# Sheet1.net
KiCad netlist of a schematic drawn in Altium Designer
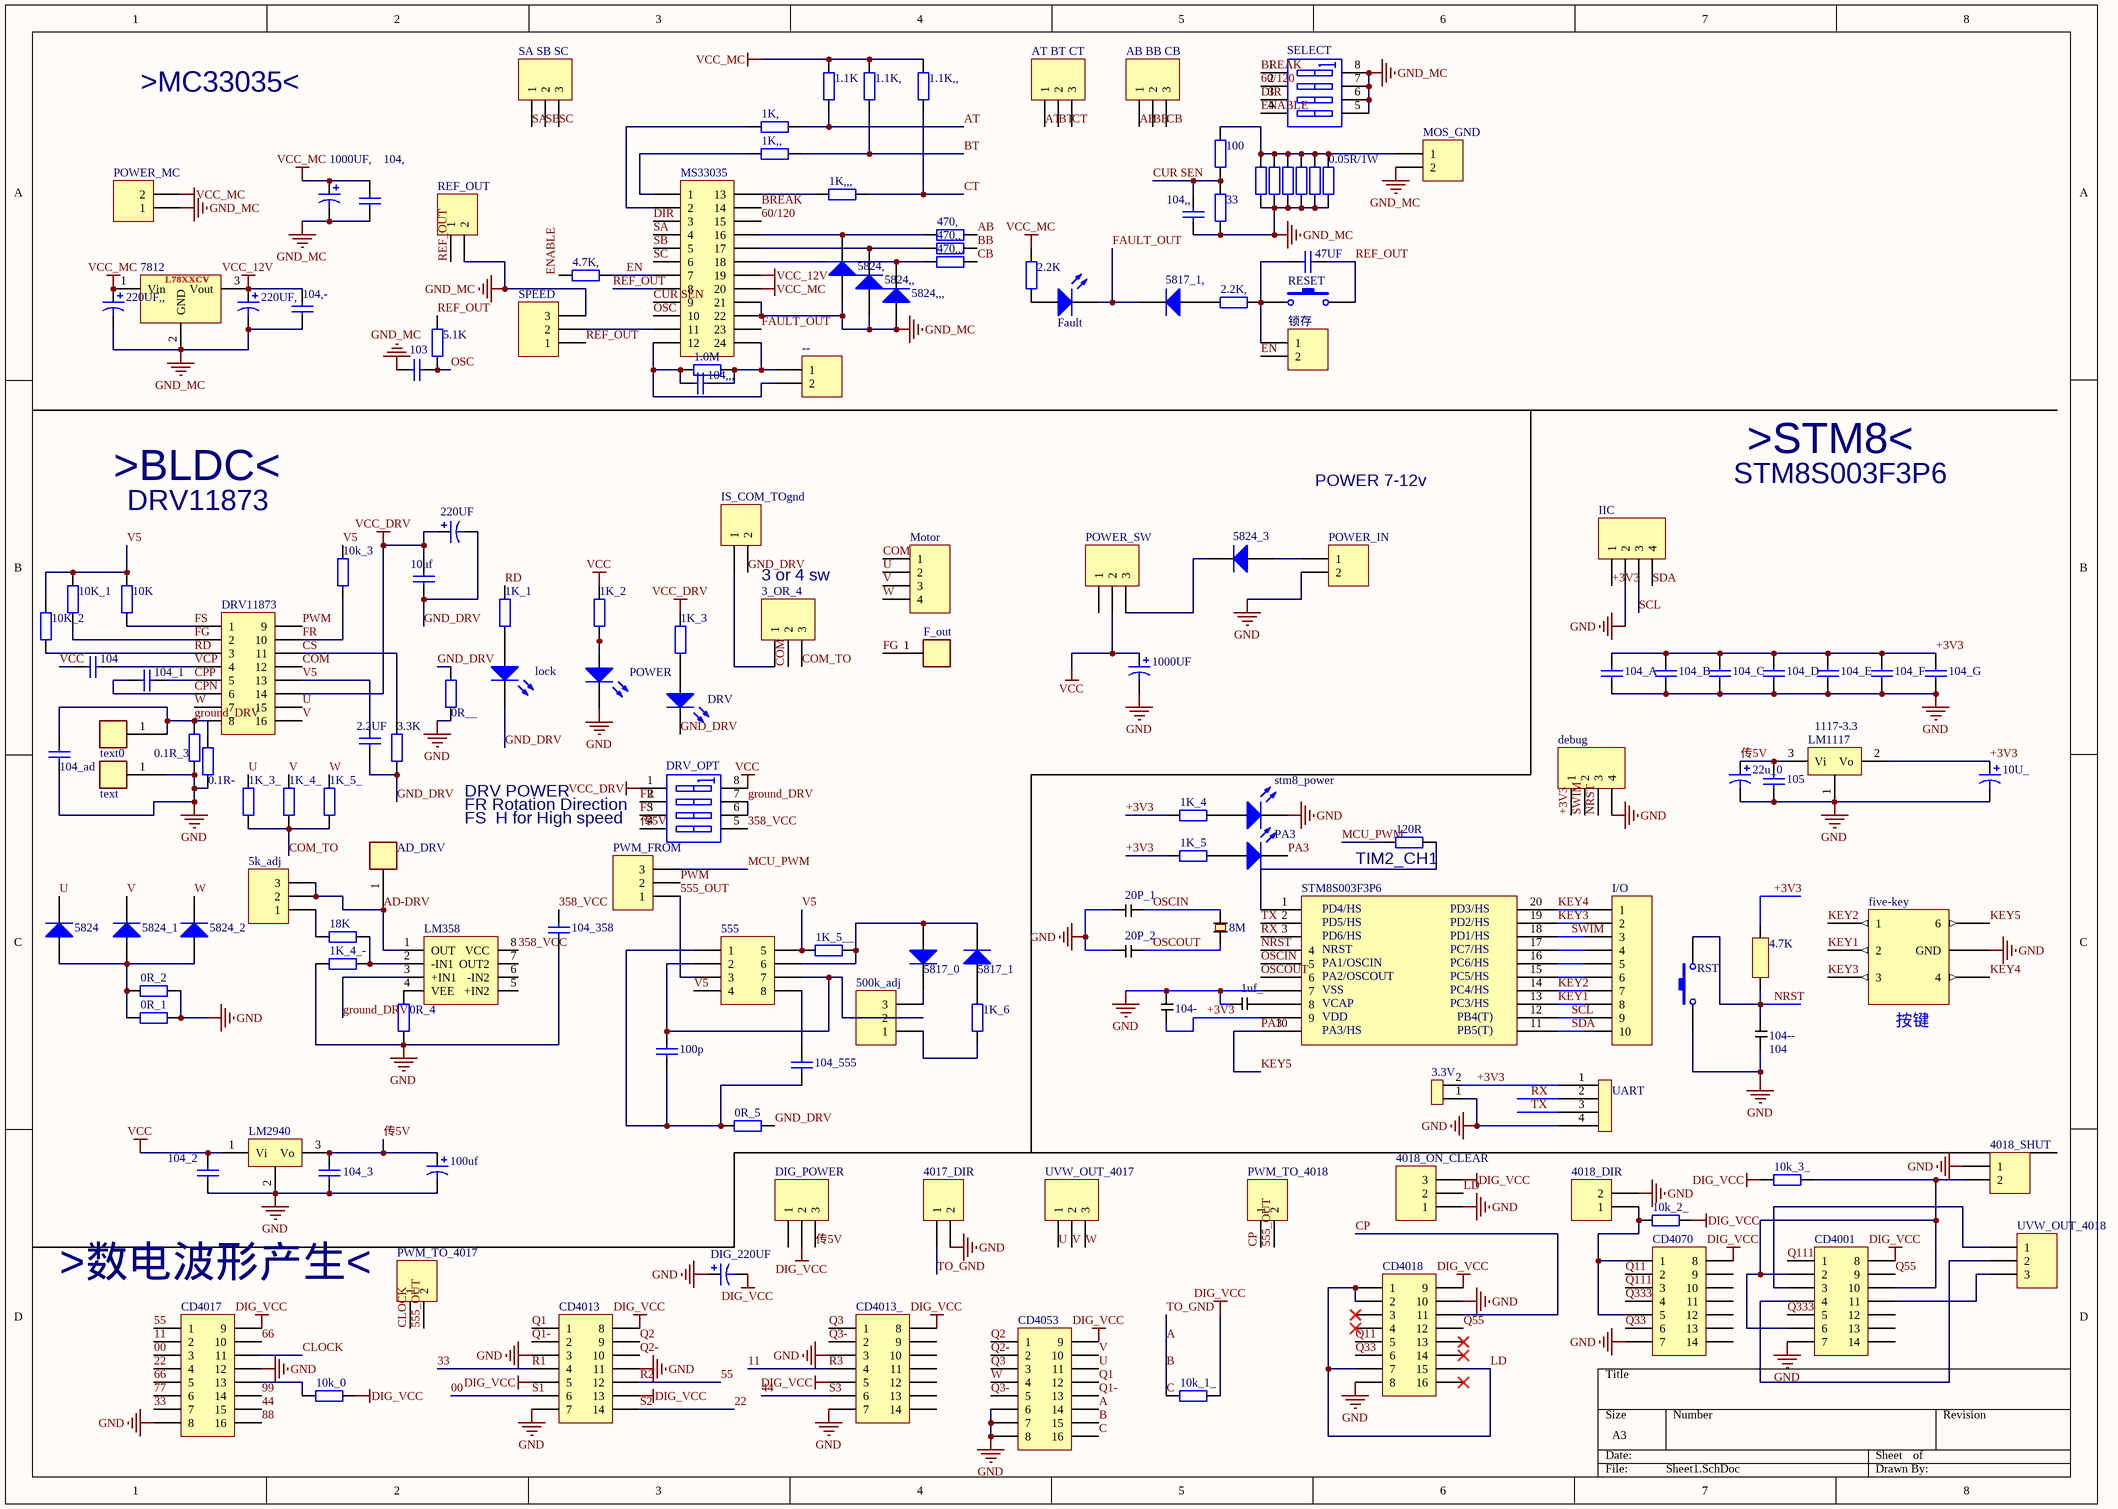
[diagram p0: Sheet1.SchDoc]

(export (version "E")
  (design (tool "Eeschema 10.0.6"))
  (components
    (comp (ref ",,")
      (value "Res2")
      (footprint "RES 0805_1")
      (description "Resistor")
      (fields (field (name "PUBLISHER") "Altium Limited"))
      (libsource (lib "") (part "Res2_3"))
    )
    (comp (ref ",,,")
      (value "Res2")
      (footprint "RES 0805_1")
      (description "Resistor")
      (fields (field (name "PUBLISHER") "Altium Limited"))
      (libsource (lib "") (part "Res2_3"))
    )
    (comp (ref ",,,,")
      (value "Res2")
      (footprint "RES 0805_1")
      (description "Resistor")
      (fields (field (name "PUBLISHER") "Altium Limited"))
      (libsource (lib "") (part "Res2_3"))
    )
    (comp (ref ",,,,,")
      (value "Res2")
      (footprint "RES 0805_1")
      (description "Resistor")
      (fields (field (name "PUBLISHER") "Altium Limited"))
      (libsource (lib "") (part "Res2_3"))
    )
    (comp (ref ",,,,,,")
      (value "Res2")
      (footprint "RES 0805_1")
      (description "Resistor")
      (fields (field (name "PUBLISHER") "Altium Limited"))
      (libsource (lib "") (part "Res2_3"))
    )
    (comp (ref "--")
      (value "Header 2")
      (footprint "HDR1X2")
      (description "Header, 2-Pin")
      (fields (field (name "PUBLISHER") "Altium Limited"))
      (libsource (lib "") (part "Header 2_1"))
    )
    (comp (ref "0.1R-")
      (value "Res2")
      (footprint "RES 0805_1")
      (description "Resistor")
      (fields (field (name "PUBLISHER") "Altium Limited"))
      (libsource (lib "") (part "Res2_1"))
    )
    (comp (ref "0.1R_3")
      (value "Res2")
      (footprint "RES 0805_1")
      (description "Resistor")
      (fields (field (name "PUBLISHER") "Altium Limited"))
      (libsource (lib "") (part "Res2_1"))
    )
    (comp (ref "0.05R/1W")
      (value "Res2")
      (footprint "RES 0805_1")
      (description "Resistor")
      (fields (field (name "PUBLISHER") "Altium Limited"))
      (libsource (lib "") (part "Res2_3"))
    )
    (comp (ref "0R_1")
      (value "Res2")
      (footprint "RES 0805_1")
      (description "Resistor")
      (fields (field (name "PUBLISHER") "Altium Limited"))
      (libsource (lib "") (part "Res2_2"))
    )
    (comp (ref "0R_2")
      (value "Res2")
      (footprint "RES 0805_1")
      (description "Resistor")
      (fields (field (name "PUBLISHER") "Altium Limited"))
      (libsource (lib "") (part "Res2_2"))
    )
    (comp (ref "0R_4")
      (value "Res2")
      (footprint "RES 0805_1")
      (description "Resistor")
      (fields (field (name "PUBLISHER") "Altium Limited"))
      (libsource (lib "") (part "Res2_3"))
    )
    (comp (ref "0R_5")
      (value "Res2")
      (footprint "RES 0805_1")
      (description "Resistor")
      (fields (field (name "PUBLISHER") "Altium Limited"))
      (libsource (lib "Miscellaneous Devices") (part "Res2"))
    )
    (comp (ref "0R__")
      (value "Res2")
      (footprint "RES 0805_1")
      (description "Resistor")
      (fields (field (name "PUBLISHER") "Altium Limited"))
      (libsource (lib "") (part "Res2_1"))
    )
    (comp (ref "1.0M")
      (value "Res2")
      (footprint "RES 0805_1")
      (description "Resistor")
      (fields (field (name "PUBLISHER") "Altium Limited"))
      (libsource (lib "Miscellaneous Devices") (part "Res2"))
    )
    (comp (ref "1.1K")
      (value "Res2")
      (footprint "RES 0805_1")
      (description "Resistor")
      (fields (field (name "PUBLISHER") "Altium Limited"))
      (libsource (lib "") (part "Res2_3"))
    )
    (comp (ref "1.1K,")
      (value "Res2")
      (footprint "RES 0805_1")
      (description "Resistor")
      (fields (field (name "PUBLISHER") "Altium Limited"))
      (libsource (lib "") (part "Res2_3"))
    )
    (comp (ref "1.1K,,")
      (value "Res2")
      (footprint "RES 0805_1")
      (description "Resistor")
      (fields (field (name "PUBLISHER") "Altium Limited"))
      (libsource (lib "") (part "Res2_3"))
    )
    (comp (ref "1K,")
      (value "Res2")
      (footprint "RES 0805_1")
      (description "Resistor")
      (fields (field (name "PUBLISHER") "Altium Limited"))
      (libsource (lib "") (part "Res2_2"))
    )
    (comp (ref "1K,,")
      (value "Res2")
      (footprint "RES 0805_1")
      (description "Resistor")
      (fields (field (name "PUBLISHER") "Altium Limited"))
      (libsource (lib "") (part "Res2_2"))
    )
    (comp (ref "1K,,,")
      (value "Res2")
      (footprint "RES 0805_1")
      (description "Resistor")
      (fields (field (name "PUBLISHER") "Altium Limited"))
      (libsource (lib "") (part "Res2_2"))
    )
    (comp (ref "1K_1")
      (value "Res2")
      (footprint "RES 0805_1")
      (description "Resistor")
      (fields (field (name "PUBLISHER") "Altium Limited"))
      (libsource (lib "") (part "Res2_1"))
    )
    (comp (ref "1K_2")
      (value "Res2")
      (footprint "RES 0805_1")
      (description "Resistor")
      (fields (field (name "PUBLISHER") "Altium Limited"))
      (libsource (lib "") (part "Res2_1"))
    )
    (comp (ref "1K_3")
      (value "Res2")
      (footprint "RES 0805_1")
      (description "Resistor")
      (fields (field (name "PUBLISHER") "Altium Limited"))
      (libsource (lib "") (part "Res2_1"))
    )
    (comp (ref "1K_3_")
      (value "Res2")
      (footprint "RES 0805_1")
      (description "Resistor")
      (fields (field (name "PUBLISHER") "Altium Limited"))
      (libsource (lib "") (part "Res2_1"))
    )
    (comp (ref "1K_4")
      (value "Res2")
      (footprint "RES 0805_1")
      (description "Resistor")
      (fields (field (name "PUBLISHER") "Altium Limited"))
      (libsource (lib "") (part "Res2_2"))
    )
    (comp (ref "1K_4_")
      (value "Res2")
      (footprint "RES 0805_1")
      (description "Resistor")
      (fields (field (name "PUBLISHER") "Altium Limited"))
      (libsource (lib "") (part "Res2_1"))
    )
    (comp (ref "1K_4_-")
      (value "Res2")
      (footprint "RES 0805_1")
      (description "Resistor")
      (fields (field (name "PUBLISHER") "Altium Limited"))
      (libsource (lib "") (part "Res2_2"))
    )
    (comp (ref "1K_5")
      (value "Res2")
      (footprint "RES 0805_1")
      (description "Resistor")
      (fields (field (name "PUBLISHER") "Altium Limited"))
      (libsource (lib "") (part "Res2_2"))
    )
    (comp (ref "1K_5_")
      (value "Res2")
      (footprint "RES 0805_1")
      (description "Resistor")
      (fields (field (name "PUBLISHER") "Altium Limited"))
      (libsource (lib "") (part "Res2_1"))
    )
    (comp (ref "1K_5__")
      (value "Res2")
      (footprint "RES 0805_1")
      (description "Resistor")
      (fields (field (name "PUBLISHER") "Altium Limited"))
      (libsource (lib "") (part "Res2_2"))
    )
    (comp (ref "1K_6")
      (value "Res2")
      (footprint "RES 0805_1")
      (description "Resistor")
      (fields (field (name "PUBLISHER") "Altium Limited"))
      (libsource (lib "") (part "Res2_3"))
    )
    (comp (ref "1uf_") (value "1UF") (footprint "0805") (libsource (lib "My_SCH_lib") (part "CAP 2")))
    (comp (ref "2.2K")
      (value "Res2")
      (footprint "RES 0805_1")
      (description "Resistor")
      (fields (field (name "PUBLISHER") "Altium Limited"))
      (libsource (lib "") (part "Res2_3"))
    )
    (comp (ref "2.2K,")
      (value "Res2")
      (footprint "RES 0805_1")
      (description "Resistor")
      (fields (field (name "PUBLISHER") "Altium Limited"))
      (libsource (lib "Miscellaneous Devices") (part "Res2"))
    )
    (comp (ref "2.2UF")
      (value "Cap")
      (footprint "0805_C")
      (description "Capacitor")
      (fields (field (name "PUBLISHER") "Altium Limited"))
      (libsource (lib "Miscellaneous Devices") (part "Cap"))
    )
    (comp (ref "3.3K")
      (value "Res2")
      (footprint "RES 0805_1")
      (description "Resistor")
      (fields (field (name "PUBLISHER") "Altium Limited"))
      (libsource (lib "") (part "Res2_1"))
    )
    (comp (ref "3.3V") (value "PIN 2") (footprint "HDR1X2") (libsource (lib "My_SCH_lib") (part "PIN 2")))
    (comp (ref "3_OR_4")
      (value "MHDR1X3")
      (footprint "MHDR1X3")
      (description "Header, 3-Pin")
      (fields (field (name "PUBLISHER") "Altium Limited"))
      (libsource (lib "") (part "MHDR1X3_1"))
    )
    (comp (ref "4.7K") (value "4.7K") (footprint "0805-1") (libsource (lib "My_SCH_lib") (part "R")))
    (comp (ref "4.7K,")
      (value "Res2")
      (footprint "RES 0805_1")
      (description "Resistor")
      (fields (field (name "PUBLISHER") "Altium Limited"))
      (libsource (lib "Miscellaneous Devices") (part "Res2"))
    )
    (comp (ref "5.1K")
      (value "Res2")
      (footprint "RES 0805_1")
      (description "Resistor")
      (fields (field (name "PUBLISHER") "Altium Limited"))
      (libsource (lib "") (part "Res2_1"))
    )
    (comp (ref "5k_adj")
      (value "Header 3")
      (footprint "pot（正方形）")
      (description "Header, 3-Pin")
      (fields (field (name "PUBLISHER") "Altium Limited"))
      (libsource (lib "") (part "Header 3_2"))
    )
    (comp (ref "8M") (value "8M") (footprint "XTAL2") (libsource (lib "My_SCH_lib") (part "XTAL")))
    (comp (ref "10K")
      (value "Res2")
      (footprint "RES 0805_1")
      (description "Resistor")
      (fields (field (name "PUBLISHER") "Altium Limited"))
      (libsource (lib "") (part "Res2_1"))
    )
    (comp (ref "10k_0")
      (value "Res2")
      (footprint "RES 0805_1")
      (description "Resistor")
      (fields (field (name "PUBLISHER") "Altium Limited"))
      (libsource (lib "Miscellaneous Devices") (part "Res2"))
    )
    (comp (ref "10K_1")
      (value "Res2")
      (footprint "RES 0805_1")
      (description "Resistor")
      (fields (field (name "PUBLISHER") "Altium Limited"))
      (libsource (lib "") (part "Res2_3"))
    )
    (comp (ref "10k_1_")
      (value "Res2")
      (footprint "RES 0805_1")
      (description "Resistor")
      (fields (field (name "PUBLISHER") "Altium Limited"))
      (libsource (lib "Miscellaneous Devices") (part "Res2"))
    )
    (comp (ref "10K_2")
      (value "Res2")
      (footprint "RES 0805_1")
      (description "Resistor")
      (fields (field (name "PUBLISHER") "Altium Limited"))
      (libsource (lib "") (part "Res2_3"))
    )
    (comp (ref "10k_2_")
      (value "Res2")
      (footprint "RES 0805_1")
      (description "Resistor")
      (fields (field (name "PUBLISHER") "Altium Limited"))
      (libsource (lib "Miscellaneous Devices") (part "Res2"))
    )
    (comp (ref "10k_3")
      (value "Res2")
      (footprint "RES 0805_1")
      (description "Resistor")
      (fields (field (name "PUBLISHER") "Altium Limited"))
      (libsource (lib "") (part "Res2_1"))
    )
    (comp (ref "10k_3_")
      (value "Res2")
      (footprint "RES 0805_1")
      (description "Resistor")
      (fields (field (name "PUBLISHER") "Altium Limited"))
      (libsource (lib "Miscellaneous Devices") (part "Res2"))
    )
    (comp (ref "10uf")
      (value "Cap")
      (footprint "0805_C")
      (description "Capacitor")
      (fields (field (name "PUBLISHER") "Altium Limited"))
      (libsource (lib "Miscellaneous Devices") (part "Cap"))
    )
    (comp (ref "10U_")
      (value "Cap Pol1")
      (footprint "0805-1")
      (description "Polarized Capacitor (Radial)")
      (fields (field (name "PUBLISHER") "Altium Limited"))
      (libsource (lib "Miscellaneous Devices") (part "Cap Pol1"))
    )
    (comp (ref "18K")
      (value "Res2")
      (footprint "RES 0805_1")
      (description "Resistor")
      (fields (field (name "PUBLISHER") "Altium Limited"))
      (libsource (lib "Miscellaneous Devices") (part "Res2"))
    )
    (comp (ref "20P_1") (value "20P") (footprint "0805") (libsource (lib "My_SCH_lib") (part "CAP 2")))
    (comp (ref "20P_2") (value "20P") (footprint "0805") (libsource (lib "My_SCH_lib") (part "CAP 2")))
    (comp (ref "22u_0")
      (value "Cap Pol1")
      (footprint "0805-1")
      (description "Polarized Capacitor (Radial)")
      (fields (field (name "PUBLISHER") "Altium Limited"))
      (libsource (lib "Miscellaneous Devices") (part "Cap Pol1"))
    )
    (comp (ref "33")
      (value "Res2")
      (footprint "RES 0805_1")
      (description "Resistor")
      (fields (field (name "PUBLISHER") "Altium Limited"))
      (libsource (lib "") (part "Res2_1"))
    )
    (comp (ref "47UF")
      (value "Cap")
      (footprint "0805_C")
      (description "Capacitor")
      (fields (field (name "PUBLISHER") "Altium Limited"))
      (libsource (lib "Miscellaneous Devices") (part "Cap"))
    )
    (comp (ref "100")
      (value "Res2")
      (footprint "RES 0805_1")
      (description "Resistor")
      (fields (field (name "PUBLISHER") "Altium Limited"))
      (libsource (lib "") (part "Res2_3"))
    )
    (comp (ref "100p")
      (value "Cap")
      (footprint "0805_C")
      (description "Capacitor")
      (fields (field (name "PUBLISHER") "Altium Limited"))
      (libsource (lib "Miscellaneous Devices") (part "Cap"))
    )
    (comp (ref "100uf")
      (value "Cap Pol1")
      (footprint "capso_8*10")
      (description "Polarized Capacitor (Radial)")
      (fields (field (name "PUBLISHER") "Altium Limited"))
      (libsource (lib "Miscellaneous Devices") (part "Cap Pol1"))
    )
    (comp (ref "103")
      (value "Cap")
      (footprint "0805_C")
      (description "Capacitor")
      (fields (field (name "PUBLISHER") "Altium Limited"))
      (libsource (lib "Miscellaneous Devices") (part "Cap"))
    )
    (comp (ref "104")
      (value "Cap")
      (footprint "0805_C")
      (description "Capacitor")
      (fields (field (name "PUBLISHER") "Altium Limited"))
      (libsource (lib "Miscellaneous Devices") (part "Cap"))
    )
    (comp (ref "104,")
      (value "Cap")
      (footprint "0805_C")
      (description "Capacitor")
      (fields (field (name "PUBLISHER") "Altium Limited"))
      (libsource (lib "Miscellaneous Devices") (part "Cap"))
    )
    (comp (ref "104,,")
      (value "Cap")
      (footprint "0805_C")
      (description "Capacitor")
      (fields (field (name "PUBLISHER") "Altium Limited"))
      (libsource (lib "Miscellaneous Devices") (part "Cap"))
    )
    (comp (ref "104,,,")
      (value "Cap")
      (footprint "0805_C")
      (description "Capacitor")
      (fields (field (name "PUBLISHER") "Altium Limited"))
      (libsource (lib "Miscellaneous Devices") (part "Cap"))
    )
    (comp (ref "104,-")
      (value "Cap")
      (footprint "0805_C")
      (description "Capacitor")
      (fields (field (name "PUBLISHER") "Altium Limited"))
      (libsource (lib "Miscellaneous Devices") (part "Cap"))
    )
    (comp (ref "104-") (value "104") (footprint "0805") (libsource (lib "My_SCH_lib") (part "CAP 2")))
    (comp (ref "104--") (value "104") (footprint "0805") (libsource (lib "My_SCH_lib") (part "CAP 2")))
    (comp (ref "104_1")
      (value "Cap")
      (footprint "0805_C")
      (description "Capacitor")
      (fields (field (name "PUBLISHER") "Altium Limited"))
      (libsource (lib "Miscellaneous Devices") (part "Cap"))
    )
    (comp (ref "104_2")
      (value "Cap")
      (footprint "0805")
      (description "Capacitor")
      (fields (field (name "PUBLISHER") "Altium Limited"))
      (libsource (lib "Miscellaneous Devices") (part "Cap"))
    )
    (comp (ref "104_3")
      (value "Cap")
      (footprint "0805")
      (description "Capacitor")
      (fields (field (name "PUBLISHER") "Altium Limited"))
      (libsource (lib "Miscellaneous Devices") (part "Cap"))
    )
    (comp (ref "104_358")
      (value "Cap")
      (footprint "0805_C")
      (description "Capacitor")
      (fields (field (name "PUBLISHER") "Altium Limited"))
      (libsource (lib "Miscellaneous Devices") (part "Cap"))
    )
    (comp (ref "104_555")
      (value "Cap")
      (footprint "0805_C")
      (description "Capacitor")
      (fields (field (name "PUBLISHER") "Altium Limited"))
      (libsource (lib "Miscellaneous Devices") (part "Cap"))
    )
    (comp (ref "104_A")
      (value "104")
      (footprint "0805")
      (description "Capacitor")
      (fields (field (name "PUBLISHER") "Altium Limited"))
      (libsource (lib "Miscellaneous Devices") (part "Cap"))
    )
    (comp (ref "104_ad")
      (value "Cap")
      (footprint "0805_C")
      (description "Capacitor")
      (fields (field (name "PUBLISHER") "Altium Limited"))
      (libsource (lib "Miscellaneous Devices") (part "Cap"))
    )
    (comp (ref "104_B")
      (value "104")
      (footprint "0805")
      (description "Capacitor")
      (fields (field (name "PUBLISHER") "Altium Limited"))
      (libsource (lib "Miscellaneous Devices") (part "Cap"))
    )
    (comp (ref "104_C")
      (value "104")
      (footprint "0805")
      (description "Capacitor")
      (fields (field (name "PUBLISHER") "Altium Limited"))
      (libsource (lib "Miscellaneous Devices") (part "Cap"))
    )
    (comp (ref "104_D")
      (value "104")
      (footprint "0805")
      (description "Capacitor")
      (fields (field (name "PUBLISHER") "Altium Limited"))
      (libsource (lib "Miscellaneous Devices") (part "Cap"))
    )
    (comp (ref "104_E")
      (value "104")
      (footprint "0805")
      (description "Capacitor")
      (fields (field (name "PUBLISHER") "Altium Limited"))
      (libsource (lib "Miscellaneous Devices") (part "Cap"))
    )
    (comp (ref "104_F")
      (value "104")
      (footprint "0805")
      (description "Capacitor")
      (fields (field (name "PUBLISHER") "Altium Limited"))
      (libsource (lib "Miscellaneous Devices") (part "Cap"))
    )
    (comp (ref "104_G")
      (value "104")
      (footprint "0805")
      (description "Capacitor")
      (fields (field (name "PUBLISHER") "Altium Limited"))
      (libsource (lib "Miscellaneous Devices") (part "Cap"))
    )
    (comp (ref "105")
      (value "105")
      (footprint "0805")
      (description "Capacitor")
      (fields (field (name "PUBLISHER") "Altium Limited"))
      (libsource (lib "Miscellaneous Devices") (part "Cap"))
    )
    (comp (ref "120R")
      (value "Res2")
      (footprint "RES 0805_1")
      (description "Resistor")
      (fields (field (name "PUBLISHER") "Altium Limited"))
      (libsource (lib "") (part "Res2_2"))
    )
    (comp (ref "220UF")
      (value "Cap Pol1")
      (footprint "capso_8*10")
      (description "Polarized Capacitor (Radial)")
      (fields (field (name "PUBLISHER") "Altium Limited"))
      (libsource (lib "Miscellaneous Devices") (part "Cap Pol1"))
    )
    (comp (ref "220UF,")
      (value "Cap Pol1")
      (footprint "capso_8*10")
      (description "Polarized Capacitor (Radial)")
      (fields (field (name "PUBLISHER") "Altium Limited"))
      (libsource (lib "Miscellaneous Devices") (part "Cap Pol1"))
    )
    (comp (ref "220UF,,")
      (value "Cap Pol1")
      (footprint "capso_8*10")
      (description "Polarized Capacitor (Radial)")
      (fields (field (name "PUBLISHER") "Altium Limited"))
      (libsource (lib "Miscellaneous Devices") (part "Cap Pol1"))
    )
    (comp (ref "470,")
      (value "Res2")
      (footprint "RES 0805_1")
      (description "Resistor")
      (fields (field (name "PUBLISHER") "Altium Limited"))
      (libsource (lib "") (part "Res2_2"))
    )
    (comp (ref "470,,")
      (value "Res2")
      (footprint "RES 0805_1")
      (description "Resistor")
      (fields (field (name "PUBLISHER") "Altium Limited"))
      (libsource (lib "") (part "Res2_2"))
    )
    (comp (ref "470,,,")
      (value "Res2")
      (footprint "RES 0805_1")
      (description "Resistor")
      (fields (field (name "PUBLISHER") "Altium Limited"))
      (libsource (lib "") (part "Res2_2"))
    )
    (comp (ref "500k_adj")
      (value "Header 3")
      (footprint "pot（正方形）")
      (description "Header, 3-Pin")
      (fields (field (name "PUBLISHER") "Altium Limited"))
      (libsource (lib "") (part "Header 3_2"))
    )
    (comp (ref "555")
      (value "Header 4X2A")
      (footprint "SOP8")
      (description "Header, 4-Pin, Dual row")
      (fields (field (name "PUBLISHER") "Altium Limited"))
      (libsource (lib "Miscellaneous Connectors") (part "Header 4X2A"))
    )
    (comp (ref "1000UF")
      (value "Cap Pol1")
      (footprint "CAPSO_10*10")
      (description "Polarized Capacitor (Radial)")
      (fields (field (name "PUBLISHER") "Altium Limited"))
      (libsource (lib "Miscellaneous Devices") (part "Cap Pol1"))
    )
    (comp (ref "1000UF,")
      (value "Cap Pol1")
      (footprint "CAPSO_10*10")
      (description "Polarized Capacitor (Radial)")
      (fields (field (name "PUBLISHER") "Altium Limited"))
      (libsource (lib "Miscellaneous Devices") (part "Cap Pol1"))
    )
    (comp (ref "1117-3.3")
      (value "LM1117")
      (footprint "SOT223")
      (libsource (lib "LM1117") (part "Component_1"))
    )
    (comp (ref "4017_DIR")
      (value "Header 2")
      (footprint "HDR1X2")
      (description "Header, 2-Pin")
      (fields (field (name "PUBLISHER") "Altium Limited"))
      (libsource (lib "") (part "Header 2_2"))
    )
    (comp (ref "4018_DIR")
      (value "Header 2")
      (footprint "HDR1X2")
      (description "Header, 2-Pin")
      (fields (field (name "PUBLISHER") "Altium Limited"))
      (libsource (lib "Miscellaneous Connectors") (part "Header 2"))
    )
    (comp (ref "4018_ON_CLEAR")
      (value "MHDR1X3")
      (footprint "MHDR1X3")
      (description "Header, 3-Pin")
      (fields (field (name "PUBLISHER") "Altium Limited"))
      (libsource (lib "Miscellaneous Connectors") (part "MHDR1X3"))
    )
    (comp (ref "4018_SHUT")
      (value "Header 2")
      (footprint "HDR1X2")
      (description "Header, 2-Pin")
      (fields (field (name "PUBLISHER") "Altium Limited"))
      (libsource (lib "") (part "Header 2_1"))
    )
    (comp (ref "5817_0")
      (value "1N5819")
      (footprint "LED_0805")
      (description "1 Amp General Purpose Rectifier")
      (fields (field (name "PUBLISHER") "Altium Limited"))
      (libsource (lib "Miscellaneous Devices") (part "Diode 1N4001"))
    )
    (comp (ref "5817_1")
      (value "1N5819")
      (footprint "LED_0805")
      (description "1 Amp General Purpose Rectifier")
      (fields (field (name "PUBLISHER") "Altium Limited"))
      (libsource (lib "Miscellaneous Devices") (part "Diode 1N4001"))
    )
    (comp (ref "5817_1,")
      (value "1N5819")
      (footprint "LED_0805")
      (description "1 Amp General Purpose Rectifier")
      (fields (field (name "PUBLISHER") "Altium Limited"))
      (libsource (lib "Miscellaneous Devices") (part "Diode 1N4001"))
    )
    (comp (ref "5824")
      (value "1N5819")
      (footprint "DIODE-SMA")
      (description "1 Amp General Purpose Rectifier")
      (fields (field (name "PUBLISHER") "Altium Limited"))
      (libsource (lib "Miscellaneous Devices") (part "Diode 1N4001"))
    )
    (comp (ref "5824,")
      (value "1N5819")
      (footprint "DIODE-SMA")
      (description "1 Amp General Purpose Rectifier")
      (fields (field (name "PUBLISHER") "Altium Limited"))
      (libsource (lib "Miscellaneous Devices") (part "Diode 1N4001"))
    )
    (comp (ref "5824,,")
      (value "1N5819")
      (footprint "DIODE-SMA")
      (description "1 Amp General Purpose Rectifier")
      (fields (field (name "PUBLISHER") "Altium Limited"))
      (libsource (lib "Miscellaneous Devices") (part "Diode 1N4001"))
    )
    (comp (ref "5824,,,")
      (value "1N5819")
      (footprint "DIODE-SMA")
      (description "1 Amp General Purpose Rectifier")
      (fields (field (name "PUBLISHER") "Altium Limited"))
      (libsource (lib "Miscellaneous Devices") (part "Diode 1N4001"))
    )
    (comp (ref "5824_1")
      (value "1N5819")
      (footprint "DIODE-SMA")
      (description "1 Amp General Purpose Rectifier")
      (fields (field (name "PUBLISHER") "Altium Limited"))
      (libsource (lib "Miscellaneous Devices") (part "Diode 1N4001"))
    )
    (comp (ref "5824_2")
      (value "1N5819")
      (footprint "DIODE-SMA")
      (description "1 Amp General Purpose Rectifier")
      (fields (field (name "PUBLISHER") "Altium Limited"))
      (libsource (lib "Miscellaneous Devices") (part "Diode 1N4001"))
    )
    (comp (ref "5824_3")
      (value "1N5819")
      (footprint "DIODE-SMA")
      (description "1 Amp General Purpose Rectifier")
      (fields (field (name "PUBLISHER") "Altium Limited"))
      (libsource (lib "Miscellaneous Devices") (part "Diode 1N4001"))
    )
    (comp (ref "7812")
      (value "L78XXCV")
      (footprint "TO-220B")
      (description "ST POSITIVE VOLTAGE REGULATORS")
      (libsource (lib "电源管理") (part "L78XXCV"))
    )
    (comp (ref "AB BB CB")
      (value "Header 3")
      (footprint "HDR1X3")
      (description "Header, 3-Pin")
      (fields (field (name "PUBLISHER") "Altium Limited"))
      (libsource (lib "Miscellaneous Connectors") (part "Header 3"))
    )
    (comp (ref "AD_DRV") (value "1PIN") (footprint "P") (libsource (lib "") (part "1PIN_2")))
    (comp (ref "AT BT CT")
      (value "Header 3")
      (footprint "HDR1X3")
      (description "Header, 3-Pin")
      (fields (field (name "PUBLISHER") "Altium Limited"))
      (libsource (lib "Miscellaneous Connectors") (part "Header 3"))
    )
    (comp (ref "CD4001")
      (value "Header 7X2A")
      (footprint "DIP14")
      (description "Header, 7-Pin, Dual row")
      (fields (field (name "PUBLISHER") "Altium Limited"))
      (libsource (lib "Miscellaneous Connectors") (part "Header 7X2A"))
    )
    (comp (ref "CD4013")
      (value "Header 7X2A")
      (footprint "SOP-14P")
      (description "Header, 7-Pin, Dual row")
      (fields (field (name "PUBLISHER") "Altium Limited"))
      (libsource (lib "Miscellaneous Connectors") (part "Header 7X2A"))
    )
    (comp (ref "CD4013_")
      (value "Header 7X2A")
      (footprint "SOP-14P")
      (description "Header, 7-Pin, Dual row")
      (fields (field (name "PUBLISHER") "Altium Limited"))
      (libsource (lib "Miscellaneous Connectors") (part "Header 7X2A"))
    )
    (comp (ref "CD4017")
      (value "Header 8X2A")
      (footprint "sop16(2003)")
      (description "Header, 8-Pin, Dual row")
      (fields (field (name "PUBLISHER") "Altium Limited"))
      (libsource (lib "Miscellaneous Connectors") (part "Header 8X2A"))
    )
    (comp (ref "CD4018")
      (value "Header 8X2A")
      (footprint "DIP16")
      (description "Header, 8-Pin, Dual row")
      (fields (field (name "PUBLISHER") "Altium Limited"))
      (libsource (lib "Miscellaneous Connectors") (part "Header 8X2A"))
    )
    (comp (ref "CD4053")
      (value "Header 8X2A")
      (footprint "sop16(2003)")
      (description "Header, 8-Pin, Dual row")
      (fields (field (name "PUBLISHER") "Altium Limited"))
      (libsource (lib "Miscellaneous Connectors") (part "Header 8X2A"))
    )
    (comp (ref "CD4070")
      (value "Header 7X2A")
      (footprint "DIP14")
      (description "Header, 7-Pin, Dual row")
      (fields (field (name "PUBLISHER") "Altium Limited"))
      (libsource (lib "Miscellaneous Connectors") (part "Header 7X2A"))
    )
    (comp (ref "debug")
      (value "Header 4")
      (footprint "HDR1X4")
      (description "Header, 4-Pin")
      (fields (field (name "PUBLISHER") "Altium Limited"))
      (libsource (lib "") (part "Header 4_1"))
    )
    (comp (ref "DIG_220UF")
      (value "Cap Pol1")
      (footprint "capso_8*10")
      (description "Polarized Capacitor (Radial)")
      (fields (field (name "PUBLISHER") "Altium Limited"))
      (libsource (lib "Miscellaneous Devices") (part "Cap Pol1"))
    )
    (comp (ref "DIG_POWER")
      (value "MHDR1X3")
      (footprint "MHDR1X3")
      (description "Header, 3-Pin")
      (fields (field (name "PUBLISHER") "Altium Limited"))
      (libsource (lib "") (part "MHDR1X3_1"))
    )
    (comp (ref "DRV") (value "LED") (footprint "LED_0805") (libsource (lib "主板库") (part "LED")))
    (comp (ref "DRV11873")
      (value "Header 8X2A")
      (footprint "TSSOP16")
      (description "Header, 8-Pin, Dual row")
      (fields (field (name "PUBLISHER") "Altium Limited"))
      (libsource (lib "Miscellaneous Connectors") (part "Header 8X2A"))
    )
    (comp (ref "DRV_OPT")
      (value "SW DIP-4")
      (footprint "SW8_4BIT")
      (description "编码开关")
      (fields (field (name "PUBLISHER") "Altium Limited"))
      (libsource (lib "Fszhang") (part "SW DIP-4"))
    )
    (comp (ref "Fault") (value "LED") (footprint "LED_0805") (libsource (lib "主板库") (part "LED")))
    (comp (ref "five-key") (value "five_key") (footprint "五向按键") (libsource (lib "VET6") (part "five_key")))
    (comp (ref "F_out") (value "1PIN") (footprint "P") (libsource (lib "") (part "1PIN_1")))
    (comp (ref "I/O")
      (value "Header 10")
      (footprint "HDR1X10")
      (description "Header, 10-Pin")
      (fields (field (name "PUBLISHER") "Altium Limited"))
      (libsource (lib "Miscellaneous Connectors") (part "Header 10"))
    )
    (comp (ref "IIC")
      (value "Header 4")
      (footprint "HDR1X4")
      (description "Header, 4-Pin")
      (fields (field (name "PUBLISHER") "Altium Limited"))
      (libsource (lib "") (part "Header 4_1"))
    )
    (comp (ref "IS_COM_TOgnd")
      (value "Header 2")
      (footprint "HDR1X2")
      (description "Header, 2-Pin")
      (fields (field (name "PUBLISHER") "Altium Limited"))
      (libsource (lib "") (part "Header 2_2"))
    )
    (comp (ref "LM358") (value "10358") (footprint "SOP8") (libsource (lib "集成块") (part "10358")))
    (comp (ref "LM2940") (value "LM2940_2") (footprint "SOT223") (libsource (lib "主板库") (part "LM2940")))
    (comp (ref "lock") (value "LED") (footprint "LED_0805") (libsource (lib "主板库") (part "LED")))
    (comp (ref "MOS_GND")
      (value "Header 2")
      (footprint "ED120/2DS_1")
      (description "Header, 2-Pin")
      (fields (field (name "PUBLISHER") "Altium Limited"))
      (libsource (lib "") (part "Header 2_1"))
    )
    (comp (ref "Motor")
      (value "Header 4")
      (footprint "ED120/4DS_1")
      (description "Header, 4-Pin")
      (fields (field (name "PUBLISHER") "Altium Limited"))
      (libsource (lib "Miscellaneous Connectors") (part "Header 4"))
    )
    (comp (ref "MS33035")
      (value "Header 12X2A")
      (footprint "SO-24W")
      (description "Header, 12-Pin, Dual row")
      (fields (field (name "PUBLISHER") "Altium Limited"))
      (libsource (lib "Miscellaneous Connectors") (part "Header 12X2A"))
    )
    (comp (ref "PA3") (value "LED") (footprint "LED_0805") (libsource (lib "主板库") (part "LED")))
    (comp (ref "POWER") (value "LED") (footprint "LED_0805") (libsource (lib "主板库") (part "LED")))
    (comp (ref "POWER_IN")
      (value "Header 2")
      (footprint "ED120/2DS_1")
      (description "Header, 2-Pin")
      (fields (field (name "PUBLISHER") "Altium Limited"))
      (libsource (lib "") (part "Header 2_1"))
    )
    (comp (ref "POWER_MC")
      (value "Header 2")
      (footprint "ED120/2DS_1")
      (description "Header, 2-Pin")
      (fields (field (name "PUBLISHER") "Altium Limited"))
      (libsource (lib "Miscellaneous Connectors") (part "Header 2"))
    )
    (comp (ref "POWER_SW")
      (value "MHDR1X3")
      (footprint "MHDR1X3")
      (description "Header, 3-Pin")
      (fields (field (name "PUBLISHER") "Altium Limited"))
      (libsource (lib "") (part "MHDR1X3_1"))
    )
    (comp (ref "PWM_FROM")
      (value "MHDR1X3")
      (footprint "MHDR1X3")
      (description "Header, 3-Pin")
      (fields (field (name "PUBLISHER") "Altium Limited"))
      (libsource (lib "Miscellaneous Connectors") (part "MHDR1X3"))
    )
    (comp (ref "PWM_TO_4017")
      (value "Header 2")
      (footprint "HDR1X2")
      (description "Header, 2-Pin")
      (fields (field (name "PUBLISHER") "Altium Limited"))
      (libsource (lib "") (part "Header 2_2"))
    )
    (comp (ref "PWM_TO_4018")
      (value "Header 2")
      (footprint "HDR1X2")
      (description "Header, 2-Pin")
      (fields (field (name "PUBLISHER") "Altium Limited"))
      (libsource (lib "") (part "Header 2_2"))
    )
    (comp (ref "REF_OUT")
      (value "Header 2")
      (footprint "HDR1X2")
      (description "Header, 2-Pin")
      (fields (field (name "PUBLISHER") "Altium Limited"))
      (libsource (lib "") (part "Header 2_2"))
    )
    (comp (ref "RESET")
      (value "SW-PB")
      (footprint "SW_PB2_A1")
      (description "微动开关")
      (fields (field (name "PUBLISHER") "Altium Limited"))
      (libsource (lib "Fszhang") (part "SW-PB"))
    )
    (comp (ref "RST")
      (value "SW-PB")
      (footprint "SW_PB2_A1")
      (description "微动开关")
      (fields (field (name "PUBLISHER") "Altium Limited"))
      (libsource (lib "Fszhang") (part "SW-PB"))
    )
    (comp (ref "SA SB SC")
      (value "Header 3")
      (footprint "HDR1X3")
      (description "Header, 3-Pin")
      (fields (field (name "PUBLISHER") "Altium Limited"))
      (libsource (lib "Miscellaneous Connectors") (part "Header 3"))
    )
    (comp (ref "SELECT")
      (value "SW DIP-4")
      (footprint "SW8_4BIT")
      (description "编码开关")
      (fields (field (name "PUBLISHER") "Altium Limited"))
      (libsource (lib "Fszhang") (part "SW DIP-4"))
    )
    (comp (ref "SPEED")
      (value "MHDR1X3")
      (footprint "pot（正方形）")
      (description "Header, 3-Pin")
      (fields (field (name "PUBLISHER") "Altium Limited"))
      (libsource (lib "Miscellaneous Connectors") (part "MHDR1X3"))
    )
    (comp (ref "STM8S003F3P6")
      (value "STM8S003F3P6")
      (footprint "TSSOP20")
      (libsource (lib "My_SCH_lib") (part "STM8S003F3P6"))
    )
    (comp (ref "stm8_power") (value "LED") (footprint "LED_0805") (libsource (lib "主板库") (part "LED")))
    (comp (ref "text") (value "1PIN") (footprint "P") (libsource (lib "常用器件库_SCH") (part "1PIN")))
    (comp (ref "text0") (value "1PIN") (footprint "P") (libsource (lib "常用器件库_SCH") (part "1PIN")))
    (comp (ref "UART") (value "PIN 4") (footprint "HDR1X4") (libsource (lib "My_SCH_lib") (part "PIN 4")))
    (comp (ref "UVW_OUT_4017")
      (value "Header 3")
      (footprint "HDR1X3")
      (description "Header, 3-Pin")
      (fields (field (name "PUBLISHER") "Altium Limited"))
      (libsource (lib "Miscellaneous Connectors") (part "Header 3"))
    )
    (comp (ref "UVW_OUT_4018")
      (value "Header 3")
      (footprint "HDR1X3")
      (description "Header, 3-Pin")
      (fields (field (name "PUBLISHER") "Altium Limited"))
      (libsource (lib "") (part "Header 3_1"))
    )
    (comp (ref "锁存")
      (value "Header 2")
      (footprint "HDR1X2")
      (description "Header, 2-Pin")
      (fields (field (name "PUBLISHER") "Altium Limited"))
      (libsource (lib "") (part "Header 2_1"))
    )
  )
  (nets
    (net (code "1") (name "/+3V3") (class "Default")
      (node (ref "104-") (pin "1") (pinfunction "1_1") (pintype "passive"))
      (node (ref "104_A") (pin "1") (pinfunction "1_1") (pintype "passive"))
      (node (ref "104_B") (pin "1") (pinfunction "1_1") (pintype "passive"))
      (node (ref "104_C") (pin "1") (pinfunction "1_1") (pintype "passive"))
      (node (ref "104_D") (pin "1") (pinfunction "1_1") (pintype "passive"))
      (node (ref "104_E") (pin "1") (pinfunction "1_1") (pintype "passive"))
      (node (ref "104_F") (pin "1") (pinfunction "1_1") (pintype "passive"))
      (node (ref "104_G") (pin "1") (pinfunction "1_1") (pintype "passive"))
      (node (ref "10U_") (pin "1") (pinfunction "1_1") (pintype "passive"))
      (node (ref "1117-3.3") (pin "2") (pinfunction "Vo_2") (pintype "passive"))
      (node (ref "1K_4") (pin "2") (pinfunction "2_2") (pintype "passive"))
      (node (ref "1K_5") (pin "2") (pinfunction "2_2") (pintype "passive"))
      (node (ref "3.3V") (pin "2") (pinfunction "2_2") (pintype "passive"))
      (node (ref "4.7K") (pin "2") (pintype "passive"))
      (node (ref "IIC") (pin "1") (pinfunction "1_1") (pintype "passive"))
      (node (ref "STM8S003F3P6") (pin "9") (pinfunction "9_9") (pintype "passive"))
      (node (ref "UART") (pin "1") (pinfunction "1_1") (pintype "passive"))
      (node (ref "debug") (pin "1") (pinfunction "1_1") (pintype "passive"))
    )
    (net (code "2") (name "/00") (class "Default")
      (node (ref "CD4013") (pin "6") (pinfunction "6_6") (pintype "passive"))
      (node (ref "CD4017") (pin "3") (pinfunction "3_3") (pintype "passive"))
    )
    (net (code "3") (name "/11") (class "Default")
      (node (ref "CD4013_") (pin "4") (pinfunction "4_4") (pintype "passive"))
      (node (ref "CD4017") (pin "2") (pinfunction "2_2") (pintype "passive"))
    )
    (net (code "4") (name "/22") (class "Default")
      (node (ref "CD4013") (pin "14") (pinfunction "14_14") (pintype "passive"))
      (node (ref "CD4017") (pin "4") (pinfunction "4_4") (pintype "passive"))
    )
    (net (code "5") (name "/33") (class "Default")
      (node (ref "CD4013") (pin "4") (pinfunction "4_4") (pintype "passive"))
      (node (ref "CD4017") (pin "7") (pinfunction "7_7") (pintype "passive"))
    )
    (net (code "6") (name "/44") (class "Default")
      (node (ref "CD4013_") (pin "6") (pinfunction "6_6") (pintype "passive"))
      (node (ref "CD4017") (pin "15") (pinfunction "15_15") (pintype "passive"))
    )
    (net (code "7") (name "/55") (class "Default")
      (node (ref "CD4013") (pin "12") (pinfunction "12_12") (pintype "passive"))
      (node (ref "CD4017") (pin "1") (pinfunction "1_1") (pintype "passive"))
    )
    (net (code "8") (name "/60{slash}120") (class "Default")
      (node (ref "MS33035") (pin "15") (pinfunction "15_15") (pintype "passive"))
      (node (ref "SELECT") (pin "2") (pinfunction "A2_2") (pintype "passive"))
    )
    (net (code "9") (name "/66") (class "Default")
      (node (ref "CD4017") (pin "10") (pinfunction "10_10") (pintype "passive"))
      (node (ref "CD4017") (pin "5") (pinfunction "5_5") (pintype "passive"))
    )
    (net (code "10") (name "/77") (class "Default")
      (node (ref "CD4017") (pin "6") (pinfunction "6_6") (pintype "passive"))
    )
    (net (code "11") (name "/88") (class "Default")
      (node (ref "CD4017") (pin "16") (pinfunction "16_16") (pintype "passive"))
    )
    (net (code "12") (name "/99") (class "Default")
      (node (ref "CD4017") (pin "14") (pinfunction "14_14") (pintype "passive"))
    )
    (net (code "13") (name "/358_VCC") (class "Default")
      (node (ref "104_358") (pin "2") (pinfunction "2_2") (pintype "passive"))
      (node (ref "DRV_OPT") (pin "5") (pinfunction "B4_5") (pintype "passive"))
      (node (ref "LM358") (pin "8") (pinfunction "VCC_8") (pintype "passive"))
    )
    (net (code "14") (name "/555_OUT") (class "Default")
      (node (ref "555") (pin "3") (pinfunction "3_3") (pintype "passive"))
      (node (ref "PWM_FROM") (pin "1") (pinfunction "1_1") (pintype "passive"))
      (node (ref "PWM_TO_4017") (pin "2") (pinfunction "2_2") (pintype "passive"))
      (node (ref "PWM_TO_4018") (pin "2") (pinfunction "2_2") (pintype "passive"))
    )
    (net (code "15") (name "/A") (class "Default")
      (node (ref "10k_1_") (pin "1") (pinfunction "1_1") (pintype "passive"))
      (node (ref "4017_DIR") (pin "1") (pinfunction "1_1") (pintype "passive"))
      (node (ref "CD4053") (pin "14") (pinfunction "14_14") (pintype "passive"))
      (node (ref "CD4053") (pin "15") (pinfunction "15_15") (pintype "passive"))
      (node (ref "CD4053") (pin "16") (pinfunction "16_16") (pintype "passive"))
    )
    (net (code "16") (name "/AB") (class "Default")
      (node (ref "470,") (pin "1") (pinfunction "1_1") (pintype "passive"))
      (node (ref "AB BB CB") (pin "1") (pinfunction "1_1") (pintype "passive"))
    )
    (net (code "17") (name "/AD-DRV") (class "Default")
      (node (ref "5k_adj") (pin "2") (pinfunction "2_2") (pintype "passive"))
      (node (ref "5k_adj") (pin "3") (pinfunction "3_3") (pintype "passive"))
      (node (ref "AD_DRV") (pin "1") (pintype "passive"))
      (node (ref "LM358") (pin "1") (pinfunction "OUT_1") (pintype "passive"))
    )
    (net (code "18") (name "/AT") (class "Default")
      (node (ref "1.1K") (pin "2") (pinfunction "2_2") (pintype "passive"))
      (node (ref "1K,") (pin "1") (pinfunction "1_1") (pintype "passive"))
      (node (ref "AT BT CT") (pin "1") (pinfunction "1_1") (pintype "passive"))
    )
    (net (code "19") (name "/BB") (class "Default")
      (node (ref "470,,") (pin "1") (pinfunction "1_1") (pintype "passive"))
      (node (ref "AB BB CB") (pin "2") (pinfunction "2_2") (pintype "passive"))
    )
    (net (code "20") (name "/BREAK") (class "Default")
      (node (ref "MS33035") (pin "14") (pinfunction "14_14") (pintype "passive"))
      (node (ref "SELECT") (pin "1") (pinfunction "A1_1") (pintype "passive"))
    )
    (net (code "21") (name "/BT") (class "Default")
      (node (ref "1.1K,") (pin "2") (pinfunction "2_2") (pintype "passive"))
      (node (ref "1K,,") (pin "1") (pinfunction "1_1") (pintype "passive"))
      (node (ref "AT BT CT") (pin "2") (pinfunction "2_2") (pintype "passive"))
    )
    (net (code "22") (name "/CB") (class "Default")
      (node (ref "470,,,") (pin "1") (pinfunction "1_1") (pintype "passive"))
      (node (ref "AB BB CB") (pin "3") (pinfunction "3_3") (pintype "passive"))
    )
    (net (code "23") (name "/CLOCK") (class "Default")
      (node (ref "CD4017") (pin "11") (pinfunction "11_11") (pintype "passive"))
      (node (ref "PWM_TO_4017") (pin "1") (pinfunction "1_1") (pintype "passive"))
    )
    (net (code "24") (name "/COM") (class "Default")
      (node (ref "3_OR_4") (pin "2") (pinfunction "2_2") (pintype "passive"))
      (node (ref "DRV11873") (pin "12") (pinfunction "12_12") (pintype "passive"))
      (node (ref "Motor") (pin "1") (pinfunction "1_1") (pintype "passive"))
    )
    (net (code "25") (name "/COM_TO") (class "Default")
      (node (ref "1K_3_") (pin "1") (pinfunction "1_1") (pintype "passive"))
      (node (ref "1K_4_") (pin "1") (pinfunction "1_1") (pintype "passive"))
      (node (ref "1K_5_") (pin "1") (pinfunction "1_1") (pintype "passive"))
      (node (ref "3_OR_4") (pin "3") (pinfunction "3_3") (pintype "passive"))
    )
    (net (code "26") (name "/CP") (class "Default")
      (node (ref "CD4018") (pin "11") (pinfunction "11_11") (pintype "passive"))
      (node (ref "PWM_TO_4018") (pin "1") (pinfunction "1_1") (pintype "passive"))
    )
    (net (code "27") (name "/CPN") (class "Default")
      (node (ref "104_1") (pin "1") (pinfunction "1_1") (pintype "passive"))
      (node (ref "DRV11873") (pin "6") (pinfunction "6_6") (pintype "passive"))
    )
    (net (code "28") (name "/CPP") (class "Default")
      (node (ref "104_1") (pin "2") (pinfunction "2_2") (pintype "passive"))
      (node (ref "DRV11873") (pin "5") (pinfunction "5_5") (pintype "passive"))
    )
    (net (code "29") (name "/CS") (class "Default")
      (node (ref "3.3K") (pin "2") (pinfunction "2_2") (pintype "passive"))
      (node (ref "DRV11873") (pin "11") (pinfunction "11_11") (pintype "passive"))
    )
    (net (code "30") (name "/CT") (class "Default")
      (node (ref "1.1K,,") (pin "2") (pinfunction "2_2") (pintype "passive"))
      (node (ref "1K,,,") (pin "1") (pinfunction "1_1") (pintype "passive"))
      (node (ref "AT BT CT") (pin "3") (pinfunction "3_3") (pintype "passive"))
    )
    (net (code "31") (name "/CUR SEN") (class "Default")
      (node (ref "100") (pin "2") (pinfunction "2_2") (pintype "passive"))
      (node (ref "104,,") (pin "1") (pinfunction "1_1") (pintype "passive"))
      (node (ref "33") (pin "2") (pinfunction "2_2") (pintype "passive"))
      (node (ref "MS33035") (pin "9") (pinfunction "9_9") (pintype "passive"))
    )
    (net (code "32") (name "/DIR") (class "Default")
      (node (ref "MS33035") (pin "3") (pinfunction "3_3") (pintype "passive"))
      (node (ref "SELECT") (pin "3") (pinfunction "A3_3") (pintype "passive"))
    )
    (net (code "33") (name "/EN") (class "Default")
      (node (ref "4.7K,") (pin "2") (pinfunction "2_2") (pintype "passive"))
      (node (ref "MS33035") (pin "7") (pinfunction "7_7") (pintype "passive"))
      (node (ref "锁存") (pin "2") (pinfunction "2_2") (pintype "passive"))
    )
    (net (code "34") (name "/ENABLE") (class "Default")
      (node (ref "4.7K,") (pin "1") (pinfunction "1_1") (pintype "passive"))
      (node (ref "SELECT") (pin "4") (pinfunction "A4_4") (pintype "passive"))
    )
    (net (code "35") (name "/FAULT_OUT") (class "Default")
      (node (ref "5817_1,") (pin "2") (pinfunction "K_2") (pintype "passive"))
      (node (ref "Fault") (pin "2") (pinfunction "K_2") (pintype "passive"))
      (node (ref "MS33035") (pin "23") (pinfunction "23_23") (pintype "passive"))
    )
    (net (code "36") (name "/FG") (class "Default")
      (node (ref "10K_1") (pin "2") (pinfunction "2_2") (pintype "passive"))
      (node (ref "DRV11873") (pin "2") (pinfunction "2_2") (pintype "passive"))
      (node (ref "F_out") (pin "1") (pintype "passive"))
    )
    (net (code "37") (name "/FR") (class "Default")
      (node (ref "10k_3") (pin "1") (pinfunction "1_1") (pintype "passive"))
      (node (ref "DRV11873") (pin "10") (pinfunction "10_10") (pintype "passive"))
      (node (ref "DRV_OPT") (pin "2") (pinfunction "A2_2") (pintype "passive"))
    )
    (net (code "38") (name "/FS") (class "Default")
      (node (ref "10K") (pin "1") (pinfunction "1_1") (pintype "passive"))
      (node (ref "DRV11873") (pin "1") (pinfunction "1_1") (pintype "passive"))
      (node (ref "DRV_OPT") (pin "3") (pinfunction "A3_3") (pintype "passive"))
    )
    (net (code "39") (name "/GND_DRV") (class "Default")
      (node (ref "0R_5") (pin "2") (pinfunction "2_2") (pintype "passive"))
      (node (ref "0R__") (pin "2") (pinfunction "2_2") (pintype "passive"))
      (node (ref "10uf") (pin "1") (pinfunction "1_1") (pintype "passive"))
      (node (ref "2.2UF") (pin "1") (pinfunction "1_1") (pintype "passive"))
      (node (ref "220UF") (pin "2") (pinfunction "2_2") (pintype "passive"))
      (node (ref "3.3K") (pin "1") (pinfunction "1_1") (pintype "passive"))
      (node (ref "DRV") (pin "2") (pinfunction "K_2") (pintype "passive"))
      (node (ref "IS_COM_TOgnd") (pin "2") (pinfunction "2_2") (pintype "passive"))
      (node (ref "lock") (pin "2") (pinfunction "K_2") (pintype "passive"))
    )
    (net (code "40") (name "/KEY1") (class "Default")
      (node (ref "I/O") (pin "8") (pinfunction "8_8") (pintype "passive"))
      (node (ref "STM8S003F3P6") (pin "13") (pinfunction "TIM1_CH3[TLI][TIM1_CH1N]_13") (pintype "passive"))
      (node (ref "five-key") (pin "2") (pinfunction "2_2") (pintype "output"))
    )
    (net (code "41") (name "/KEY2") (class "Default")
      (node (ref "I/O") (pin "7") (pinfunction "7_7") (pintype "passive"))
      (node (ref "STM8S003F3P6") (pin "14") (pinfunction "TIM1_CH4/CLK_CCO/AIN2[TIM1_CH2N]_14") (pintype "passive"))
      (node (ref "five-key") (pin "1") (pinfunction "1_1") (pintype "output"))
    )
    (net (code "42") (name "/KEY3") (class "Default")
      (node (ref "I/O") (pin "2") (pinfunction "2_2") (pintype "passive"))
      (node (ref "STM8S003F3P6") (pin "19") (pinfunction "AIN3[TIM2_CH3]_19") (pintype "passive"))
      (node (ref "five-key") (pin "3") (pinfunction "3_3") (pintype "output"))
    )
    (net (code "43") (name "/KEY4") (class "Default")
      (node (ref "I/O") (pin "1") (pinfunction "1_1") (pintype "passive"))
      (node (ref "STM8S003F3P6") (pin "20") (pinfunction "AIN4/TIM2_CH2/ADC_ETR_20") (pintype "passive"))
      (node (ref "five-key") (pin "4") (pinfunction "4_4") (pintype "output"))
    )
    (net (code "44") (name "/KEY5") (class "Default")
      (node (ref "PA3") (pin "2") (pinfunction "K_2") (pintype "passive"))
      (node (ref "STM8S003F3P6") (pin "10") (pinfunction "[SPI_NSS]TIM2_CH3/HS_10") (pintype "passive"))
      (node (ref "five-key") (pin "6") (pinfunction "6_6") (pintype "output"))
    )
    (net (code "45") (name "/LD") (class "Default")
      (node (ref "4018_ON_CLEAR") (pin "2") (pinfunction "2_2") (pintype "passive"))
      (node (ref "CD4018") (pin "1") (pinfunction "1_1") (pintype "passive"))
      (node (ref "CD4018") (pin "15") (pinfunction "15_15") (pintype "passive"))
      (node (ref "CD4018") (pin "2") (pinfunction "2_2") (pintype "passive"))
      (node (ref "CD4018") (pin "7") (pinfunction "7_7") (pintype "passive"))
    )
    (net (code "46") (name "/MCU_PWM") (class "Default")
      (node (ref "120R") (pin "2") (pinfunction "2_2") (pintype "passive"))
      (node (ref "PWM_FROM") (pin "3") (pinfunction "3_3") (pintype "passive"))
    )
    (net (code "47") (name "/NRST") (class "Default")
      (node (ref "104--") (pin "2") (pinfunction "2_2") (pintype "passive"))
      (node (ref "4.7K") (pin "1") (pintype "passive"))
      (node (ref "RST") (pin "2") (pinfunction "2_2") (pintype "passive"))
      (node (ref "STM8S003F3P6") (pin "4") (pinfunction "4_4") (pintype "passive"))
      (node (ref "debug") (pin "3") (pinfunction "3_3") (pintype "passive"))
    )
    (net (code "48") (name "/OSC") (class "Default")
      (node (ref "103") (pin "1") (pinfunction "1_1") (pintype "passive"))
      (node (ref "5.1K") (pin "1") (pinfunction "1_1") (pintype "passive"))
      (node (ref "MS33035") (pin "10") (pinfunction "10_10") (pintype "passive"))
    )
    (net (code "49") (name "/OSCIN") (class "Default")
      (node (ref "20P_1") (pin "2") (pinfunction "2_2") (pintype "passive"))
      (node (ref "8M") (pin "2") (pinfunction "2_2") (pintype "passive"))
      (node (ref "STM8S003F3P6") (pin "5") (pinfunction "5_5") (pintype "passive"))
    )
    (net (code "50") (name "/OSCOUT") (class "Default")
      (node (ref "20P_2") (pin "2") (pinfunction "2_2") (pintype "passive"))
      (node (ref "8M") (pin "1") (pinfunction "1_1") (pintype "passive"))
      (node (ref "STM8S003F3P6") (pin "6") (pinfunction "6_6") (pintype "passive"))
    )
    (net (code "51") (name "/PWM") (class "Default")
      (node (ref "DRV11873") (pin "9") (pinfunction "9_9") (pintype "passive"))
      (node (ref "PWM_FROM") (pin "2") (pinfunction "2_2") (pintype "passive"))
    )
    (net (code "52") (name "/Q1") (class "Default")
      (node (ref "CD4013") (pin "1") (pinfunction "1_1") (pintype "passive"))
      (node (ref "CD4053") (pin "12") (pinfunction "12_12") (pintype "passive"))
    )
    (net (code "53") (name "/Q1-") (class "Default")
      (node (ref "CD4013") (pin "2") (pinfunction "2_2") (pintype "passive"))
      (node (ref "CD4053") (pin "13") (pinfunction "13_13") (pintype "passive"))
    )
    (net (code "54") (name "/Q2") (class "Default")
      (node (ref "CD4013") (pin "9") (pinfunction "9_9") (pintype "passive"))
      (node (ref "CD4053") (pin "1") (pinfunction "1_1") (pintype "passive"))
    )
    (net (code "55") (name "/Q2-") (class "Default")
      (node (ref "CD4013") (pin "10") (pinfunction "10_10") (pintype "passive"))
      (node (ref "CD4053") (pin "2") (pinfunction "2_2") (pintype "passive"))
    )
    (net (code "56") (name "/Q3") (class "Default")
      (node (ref "CD4013_") (pin "1") (pinfunction "1_1") (pintype "passive"))
      (node (ref "CD4053") (pin "3") (pinfunction "3_3") (pintype "passive"))
    )
    (net (code "57") (name "/Q3-") (class "Default")
      (node (ref "CD4013_") (pin "2") (pinfunction "2_2") (pintype "passive"))
      (node (ref "CD4053") (pin "5") (pinfunction "5_5") (pintype "passive"))
    )
    (net (code "58") (name "/Q11") (class "Default")
      (node (ref "CD4018") (pin "5") (pinfunction "5_5") (pintype "passive"))
      (node (ref "CD4070") (pin "2") (pinfunction "2_2") (pintype "passive"))
    )
    (net (code "59") (name "/Q33") (class "Default")
      (node (ref "CD4018") (pin "6") (pinfunction "6_6") (pintype "passive"))
      (node (ref "CD4070") (pin "6") (pinfunction "6_6") (pintype "passive"))
    )
    (net (code "60") (name "/Q55") (class "Default")
      (node (ref "CD4001") (pin "9") (pinfunction "9_9") (pintype "passive"))
      (node (ref "CD4018") (pin "12") (pinfunction "12_12") (pintype "passive"))
    )
    (net (code "61") (name "/Q111") (class "Default")
      (node (ref "CD4001") (pin "1") (pinfunction "1_1") (pintype "passive"))
      (node (ref "CD4070") (pin "3") (pinfunction "3_3") (pintype "passive"))
    )
    (net (code "62") (name "/Q333") (class "Default")
      (node (ref "CD4001") (pin "5") (pinfunction "5_5") (pintype "passive"))
      (node (ref "CD4070") (pin "4") (pinfunction "4_4") (pintype "passive"))
    )
    (net (code "63") (name "/RD") (class "Default")
      (node (ref "10K_2") (pin "2") (pinfunction "2_2") (pintype "passive"))
      (node (ref "1K_1") (pin "2") (pinfunction "2_2") (pintype "passive"))
      (node (ref "DRV11873") (pin "3") (pinfunction "3_3") (pintype "passive"))
    )
    (net (code "64") (name "/REF_OUT") (class "Default")
      (node (ref "47UF") (pin "1") (pinfunction "1_1") (pintype "passive"))
      (node (ref "5.1K") (pin "2") (pinfunction "2_2") (pintype "passive"))
      (node (ref "MS33035") (pin "8") (pinfunction "8_8") (pintype "passive"))
      (node (ref "REF_OUT") (pin "1") (pinfunction "1_1") (pintype "passive"))
      (node (ref "RESET") (pin "2") (pinfunction "2_2") (pintype "passive"))
      (node (ref "SPEED") (pin "1") (pinfunction "1_1") (pintype "passive"))
    )
    (net (code "65") (name "/RX") (class "Default")
      (node (ref "STM8S003F3P6") (pin "3") (pinfunction "UART1_RX/AIN6/HS_3") (pintype "passive"))
      (node (ref "UART") (pin "2") (pinfunction "2_2") (pintype "passive"))
    )
    (net (code "66") (name "/SA") (class "Default")
      (node (ref "MS33035") (pin "4") (pinfunction "4_4") (pintype "passive"))
      (node (ref "SA SB SC") (pin "1") (pinfunction "1_1") (pintype "passive"))
    )
    (net (code "67") (name "/SB") (class "Default")
      (node (ref "MS33035") (pin "5") (pinfunction "5_5") (pintype "passive"))
      (node (ref "SA SB SC") (pin "2") (pinfunction "2_2") (pintype "passive"))
    )
    (net (code "68") (name "/SC") (class "Default")
      (node (ref "MS33035") (pin "6") (pinfunction "6_6") (pintype "passive"))
      (node (ref "SA SB SC") (pin "3") (pinfunction "3_3") (pintype "passive"))
    )
    (net (code "69") (name "/SCL") (class "Default")
      (node (ref "I/O") (pin "9") (pinfunction "9_9") (pintype "passive"))
      (node (ref "IIC") (pin "3") (pinfunction "3_3") (pintype "passive"))
      (node (ref "STM8S003F3P6") (pin "12") (pinfunction "I2C_SCL[ADC_ETR]_12") (pintype "passive"))
    )
    (net (code "70") (name "/SDA") (class "Default")
      (node (ref "I/O") (pin "10") (pinfunction "10_10") (pintype "passive"))
      (node (ref "IIC") (pin "4") (pinfunction "4_4") (pintype "passive"))
      (node (ref "STM8S003F3P6") (pin "11") (pinfunction "I2C_SDA[TIM1_BKIN]_11") (pintype "passive"))
    )
    (net (code "71") (name "/SWIM") (class "Default")
      (node (ref "I/O") (pin "3") (pinfunction "3_3") (pintype "passive"))
      (node (ref "STM8S003F3P6") (pin "18") (pinfunction "SWIM_18") (pintype "passive"))
      (node (ref "debug") (pin "2") (pinfunction "2_2") (pintype "passive"))
    )
    (net (code "72") (name "/TX") (class "Default")
      (node (ref "STM8S003F3P6") (pin "2") (pinfunction "UART1_TX/AIN5/HS_2") (pintype "passive"))
      (node (ref "UART") (pin "3") (pinfunction "3_3") (pintype "passive"))
    )
    (net (code "73") (name "/U") (class "Default")
      (node (ref "1K_3_") (pin "2") (pinfunction "2_2") (pintype "passive"))
      (node (ref "5824") (pin "2") (pinfunction "K_2") (pintype "passive"))
      (node (ref "CD4053") (pin "11") (pinfunction "11_11") (pintype "passive"))
      (node (ref "DRV11873") (pin "15") (pinfunction "15_15") (pintype "passive"))
      (node (ref "Motor") (pin "2") (pinfunction "2_2") (pintype "passive"))
      (node (ref "UVW_OUT_4017") (pin "1") (pinfunction "1_1") (pintype "passive"))
    )
    (net (code "74") (name "/V") (class "Default")
      (node (ref "1K_4_") (pin "2") (pinfunction "2_2") (pintype "passive"))
      (node (ref "5824_1") (pin "2") (pinfunction "K_2") (pintype "passive"))
      (node (ref "CD4053") (pin "10") (pinfunction "10_10") (pintype "passive"))
      (node (ref "DRV11873") (pin "16") (pinfunction "16_16") (pintype "passive"))
      (node (ref "Motor") (pin "3") (pinfunction "3_3") (pintype "passive"))
      (node (ref "UVW_OUT_4017") (pin "2") (pinfunction "2_2") (pintype "passive"))
    )
    (net (code "75") (name "/V5") (class "Default")
      (node (ref "10K") (pin "2") (pinfunction "2_2") (pintype "passive"))
      (node (ref "10K_1") (pin "1") (pinfunction "1_1") (pintype "passive"))
      (node (ref "10K_2") (pin "1") (pinfunction "1_1") (pintype "passive"))
      (node (ref "10k_3") (pin "2") (pinfunction "2_2") (pintype "passive"))
      (node (ref "1K_5__") (pin "2") (pinfunction "2_2") (pintype "passive"))
      (node (ref "2.2UF") (pin "2") (pinfunction "2_2") (pintype "passive"))
      (node (ref "555") (pin "4") (pinfunction "4_4") (pintype "passive"))
      (node (ref "555") (pin "5") (pinfunction "5_5") (pintype "passive"))
      (node (ref "DRV11873") (pin "13") (pinfunction "13_13") (pintype "passive"))
    )
    (net (code "76") (name "/VCP") (class "Default")
      (node (ref "104") (pin "2") (pinfunction "2_2") (pintype "passive"))
      (node (ref "DRV11873") (pin "4") (pinfunction "4_4") (pintype "passive"))
    )
    (net (code "77") (name "/W") (class "Default")
      (node (ref "1K_5_") (pin "2") (pinfunction "2_2") (pintype "passive"))
      (node (ref "5824_2") (pin "2") (pinfunction "K_2") (pintype "passive"))
      (node (ref "CD4053") (pin "4") (pinfunction "4_4") (pintype "passive"))
      (node (ref "DRV11873") (pin "7") (pinfunction "7_7") (pintype "passive"))
      (node (ref "Motor") (pin "4") (pinfunction "4_4") (pintype "passive"))
      (node (ref "UVW_OUT_4017") (pin "3") (pinfunction "3_3") (pintype "passive"))
    )
    (net (code "78") (name "/ground_DRV") (class "Default")
      (node (ref "0.1R-") (pin "2") (pinfunction "2_2") (pintype "passive"))
      (node (ref "0.1R_3") (pin "2") (pinfunction "2_2") (pintype "passive"))
      (node (ref "104_ad") (pin "2") (pinfunction "2_2") (pintype "passive"))
      (node (ref "DRV11873") (pin "8") (pinfunction "8_8") (pintype "passive"))
      (node (ref "DRV_OPT") (pin "6") (pinfunction "B3_6") (pintype "passive"))
      (node (ref "DRV_OPT") (pin "7") (pinfunction "B2_7") (pintype "passive"))
      (node (ref "LM358") (pin "3") (pinfunction "+IN1_3") (pintype "passive"))
      (node (ref "text0") (pin "1") (pintype "passive"))
    )
    (net (code "79") (name "/传5V") (class "Default")
      (node (ref "100uf") (pin "1") (pinfunction "1_1") (pintype "passive"))
      (node (ref "104_3") (pin "2") (pinfunction "2_2") (pintype "passive"))
      (node (ref "105") (pin "1") (pinfunction "1_1") (pintype "passive"))
      (node (ref "1117-3.3") (pin "3") (pinfunction "Vi_3") (pintype "passive"))
      (node (ref "22u_0") (pin "1") (pinfunction "1_1") (pintype "passive"))
      (node (ref "DIG_POWER") (pin "3") (pinfunction "3_3") (pintype "passive"))
      (node (ref "DRV_OPT") (pin "4") (pinfunction "A4_4") (pintype "passive"))
      (node (ref "LM2940") (pin "3") (pinfunction "Vo_3") (pintype "passive"))
    )
    (net (code "80") (name "DIG_VCC") (class "Default")
      (node (ref "10k_0") (pin "2") (pinfunction "2_2") (pintype "passive"))
      (node (ref "10k_1_") (pin "2") (pinfunction "2_2") (pintype "passive"))
      (node (ref "10k_2_") (pin "2") (pinfunction "2_2") (pintype "passive"))
      (node (ref "10k_3_") (pin "1") (pinfunction "1_1") (pintype "passive"))
      (node (ref "4018_ON_CLEAR") (pin "3") (pinfunction "3_3") (pintype "passive"))
      (node (ref "CD4001") (pin "8") (pinfunction "8_8") (pintype "passive"))
      (node (ref "CD4013") (pin "13") (pinfunction "13_13") (pintype "passive"))
      (node (ref "CD4013") (pin "5") (pinfunction "5_5") (pintype "passive"))
      (node (ref "CD4013") (pin "8") (pinfunction "8_8") (pintype "passive"))
      (node (ref "CD4013_") (pin "5") (pinfunction "5_5") (pintype "passive"))
      (node (ref "CD4013_") (pin "8") (pinfunction "8_8") (pintype "passive"))
      (node (ref "CD4017") (pin "9") (pinfunction "9_9") (pintype "passive"))
      (node (ref "CD4018") (pin "9") (pinfunction "9_9") (pintype "passive"))
      (node (ref "CD4053") (pin "9") (pinfunction "9_9") (pintype "passive"))
      (node (ref "CD4070") (pin "8") (pinfunction "8_8") (pintype "passive"))
      (node (ref "DIG_220UF") (pin "2") (pinfunction "2_2") (pintype "passive"))
      (node (ref "DIG_POWER") (pin "2") (pinfunction "2_2") (pintype "passive"))
    )
    (net (code "81") (name "GND") (class "Default")
      (node (ref "0.1R-") (pin "1") (pinfunction "1_1") (pintype "passive"))
      (node (ref "0.1R_3") (pin "1") (pinfunction "1_1") (pintype "passive"))
      (node (ref "0R_1") (pin "1") (pinfunction "1_1") (pintype "passive"))
      (node (ref "0R_2") (pin "1") (pinfunction "1_1") (pintype "passive"))
      (node (ref "0R_4") (pin "2") (pinfunction "2_2") (pintype "passive"))
      (node (ref "0R__") (pin "1") (pinfunction "1_1") (pintype "passive"))
      (node (ref "1000UF") (pin "2") (pinfunction "2_2") (pintype "passive"))
      (node (ref "100uf") (pin "2") (pinfunction "2_2") (pintype "passive"))
      (node (ref "104-") (pin "2") (pinfunction "2_2") (pintype "passive"))
      (node (ref "104--") (pin "1") (pinfunction "1_1") (pintype "passive"))
      (node (ref "104_2") (pin "1") (pinfunction "1_1") (pintype "passive"))
      (node (ref "104_3") (pin "1") (pinfunction "1_1") (pintype "passive"))
      (node (ref "104_358") (pin "1") (pinfunction "1_1") (pintype "passive"))
      (node (ref "104_A") (pin "2") (pinfunction "2_2") (pintype "passive"))
      (node (ref "104_B") (pin "2") (pinfunction "2_2") (pintype "passive"))
      (node (ref "104_C") (pin "2") (pinfunction "2_2") (pintype "passive"))
      (node (ref "104_D") (pin "2") (pinfunction "2_2") (pintype "passive"))
      (node (ref "104_E") (pin "2") (pinfunction "2_2") (pintype "passive"))
      (node (ref "104_F") (pin "2") (pinfunction "2_2") (pintype "passive"))
      (node (ref "104_G") (pin "2") (pinfunction "2_2") (pintype "passive"))
      (node (ref "104_ad") (pin "1") (pinfunction "1_1") (pintype "passive"))
      (node (ref "105") (pin "2") (pinfunction "2_2") (pintype "passive"))
      (node (ref "10U_") (pin "2") (pinfunction "2_2") (pintype "passive"))
      (node (ref "1117-3.3") (pin "1") (pinfunction "COM_1") (pintype "passive"))
      (node (ref "1K_4_-") (pin "2") (pinfunction "2_2") (pintype "passive"))
      (node (ref "1uf_") (pin "2") (pinfunction "2_2") (pintype "passive"))
      (node (ref "20P_1") (pin "1") (pinfunction "1_1") (pintype "passive"))
      (node (ref "20P_2") (pin "1") (pinfunction "1_1") (pintype "passive"))
      (node (ref "22u_0") (pin "2") (pinfunction "2_2") (pintype "passive"))
      (node (ref "3.3V") (pin "1") (pinfunction "1_1") (pintype "passive"))
      (node (ref "4017_DIR") (pin "2") (pinfunction "2_2") (pintype "passive"))
      (node (ref "4018_DIR") (pin "2") (pinfunction "2_2") (pintype "passive"))
      (node (ref "4018_ON_CLEAR") (pin "1") (pinfunction "1_1") (pintype "passive"))
      (node (ref "4018_SHUT") (pin "1") (pinfunction "1_1") (pintype "passive"))
      (node (ref "CD4001") (pin "7") (pinfunction "7_7") (pintype "passive"))
      (node (ref "CD4013") (pin "11") (pinfunction "11_11") (pintype "passive"))
      (node (ref "CD4013") (pin "3") (pinfunction "3_3") (pintype "passive"))
      (node (ref "CD4013") (pin "7") (pinfunction "7_7") (pintype "passive"))
      (node (ref "CD4013_") (pin "3") (pinfunction "3_3") (pintype "passive"))
      (node (ref "CD4013_") (pin "7") (pinfunction "7_7") (pintype "passive"))
      (node (ref "CD4017") (pin "12") (pinfunction "12_12") (pintype "passive"))
      (node (ref "CD4017") (pin "8") (pinfunction "8_8") (pintype "passive"))
      (node (ref "CD4018") (pin "10") (pinfunction "10_10") (pintype "passive"))
      (node (ref "CD4018") (pin "8") (pinfunction "8_8") (pintype "passive"))
      (node (ref "CD4053") (pin "6") (pinfunction "6_6") (pintype "passive"))
      (node (ref "CD4053") (pin "7") (pinfunction "7_7") (pintype "passive"))
      (node (ref "CD4053") (pin "8") (pinfunction "8_8") (pintype "passive"))
      (node (ref "CD4070") (pin "7") (pinfunction "7_7") (pintype "passive"))
      (node (ref "DIG_220UF") (pin "1") (pinfunction "1_1") (pintype "passive"))
      (node (ref "IIC") (pin "2") (pinfunction "2_2") (pintype "passive"))
      (node (ref "LM2940") (pin "2") (pinfunction "2_2") (pintype "passive"))
      (node (ref "POWER") (pin "2") (pinfunction "K_2") (pintype "passive"))
      (node (ref "POWER_IN") (pin "2") (pinfunction "2_2") (pintype "passive"))
      (node (ref "RST") (pin "1") (pinfunction "1_1") (pintype "passive"))
      (node (ref "STM8S003F3P6") (pin "7") (pinfunction "7_7") (pintype "passive"))
      (node (ref "UART") (pin "4") (pinfunction "4_4") (pintype "passive"))
      (node (ref "debug") (pin "4") (pinfunction "4_4") (pintype "passive"))
      (node (ref "five-key") (pin "5") (pinfunction "GND_5") (pintype "power_in"))
      (node (ref "stm8_power") (pin "2") (pinfunction "K_2") (pintype "passive"))
      (node (ref "text") (pin "1") (pintype "passive"))
    )
    (net (code "82") (name "GND_MC") (class "Default")
      (node (ref ",,") (pin "2") (pinfunction "2_2") (pintype "passive"))
      (node (ref ",,,") (pin "2") (pinfunction "2_2") (pintype "passive"))
      (node (ref ",,,,") (pin "2") (pinfunction "2_2") (pintype "passive"))
      (node (ref ",,,,,") (pin "2") (pinfunction "2_2") (pintype "passive"))
      (node (ref ",,,,,,") (pin "2") (pinfunction "2_2") (pintype "passive"))
      (node (ref "0.05R/1W") (pin "2") (pinfunction "2_2") (pintype "passive"))
      (node (ref "1000UF,") (pin "2") (pinfunction "2_2") (pintype "passive"))
      (node (ref "103") (pin "2") (pinfunction "2_2") (pintype "passive"))
      (node (ref "104,") (pin "1") (pinfunction "1_1") (pintype "passive"))
      (node (ref "104,,") (pin "2") (pinfunction "2_2") (pintype "passive"))
      (node (ref "104,-") (pin "1") (pinfunction "1_1") (pintype "passive"))
      (node (ref "220UF,") (pin "2") (pinfunction "2_2") (pintype "passive"))
      (node (ref "220UF,,") (pin "2") (pinfunction "2_2") (pintype "passive"))
      (node (ref "33") (pin "1") (pinfunction "1_1") (pintype "passive"))
      (node (ref "5824,") (pin "1") (pinfunction "A_1") (pintype "passive"))
      (node (ref "5824,,") (pin "1") (pinfunction "A_1") (pintype "passive"))
      (node (ref "5824,,,") (pin "1") (pinfunction "A_1") (pintype "passive"))
      (node (ref "7812") (pin "2") (pinfunction "GND_2") (pintype "passive"))
      (node (ref "MOS_GND") (pin "2") (pinfunction "2_2") (pintype "passive"))
      (node (ref "MS33035") (pin "21") (pinfunction "21_21") (pintype "passive"))
      (node (ref "MS33035") (pin "22") (pinfunction "22_22") (pintype "passive"))
      (node (ref "POWER_MC") (pin "1") (pinfunction "1_1") (pintype "passive"))
      (node (ref "REF_OUT") (pin "2") (pinfunction "2_2") (pintype "passive"))
      (node (ref "SELECT") (pin "5") (pinfunction "B4_5") (pintype "passive"))
      (node (ref "SELECT") (pin "6") (pinfunction "B3_6") (pintype "passive"))
      (node (ref "SELECT") (pin "7") (pinfunction "B2_7") (pintype "passive"))
      (node (ref "SELECT") (pin "8") (pinfunction "B1_8") (pintype "passive"))
      (node (ref "SPEED") (pin "3") (pinfunction "3_3") (pintype "passive"))
    )
    (net (code "83") (name "Net-(,,,,,,-Pad1)") (class "Default")
      (node (ref ",,") (pin "1") (pinfunction "1_1") (pintype "passive"))
      (node (ref ",,,") (pin "1") (pinfunction "1_1") (pintype "passive"))
      (node (ref ",,,,") (pin "1") (pinfunction "1_1") (pintype "passive"))
      (node (ref ",,,,,") (pin "1") (pinfunction "1_1") (pintype "passive"))
      (node (ref ",,,,,,") (pin "1") (pinfunction "1_1") (pintype "passive"))
      (node (ref "0.05R/1W") (pin "1") (pinfunction "1_1") (pintype "passive"))
      (node (ref "100") (pin "1") (pinfunction "1_1") (pintype "passive"))
      (node (ref "MOS_GND") (pin "1") (pinfunction "1_1") (pintype "passive"))
    )
    (net (code "84") (name "Net-(---Pad1)") (class "Default")
      (node (ref "--") (pin "1") (pinfunction "1_1") (pintype "passive"))
      (node (ref "1.0M") (pin "2") (pinfunction "2_2") (pintype "passive"))
      (node (ref "104,,,") (pin "1") (pinfunction "1_1") (pintype "passive"))
      (node (ref "MS33035") (pin "24") (pinfunction "24_24") (pintype "passive"))
    )
    (net (code "85") (name "Net-(---Pad2)") (class "Default")
      (node (ref "--") (pin "2") (pinfunction "2_2") (pintype "passive"))
      (node (ref "1.0M") (pin "1") (pinfunction "1_1") (pintype "passive"))
      (node (ref "104,,,") (pin "2") (pinfunction "2_2") (pintype "passive"))
      (node (ref "MS33035") (pin "12") (pinfunction "12_12") (pintype "passive"))
    )
    (net (code "86") (name "Net-(0R_5-Pad1)") (class "Default")
      (node (ref "0R_5") (pin "1") (pinfunction "1_1") (pintype "passive"))
      (node (ref "100p") (pin "1") (pinfunction "1_1") (pintype "passive"))
      (node (ref "104_555") (pin "1") (pinfunction "1_1") (pintype "passive"))
      (node (ref "555") (pin "1") (pinfunction "1_1") (pintype "passive"))
    )
    (net (code "87") (name "Net-(1K,,,-Pad2)") (class "Default")
      (node (ref "1K,,,") (pin "2") (pinfunction "2_2") (pintype "passive"))
      (node (ref "MS33035") (pin "13") (pinfunction "13_13") (pintype "passive"))
    )
    (net (code "88") (name "Net-(1K,,-Pad2)") (class "Default")
      (node (ref "1K,,") (pin "2") (pinfunction "2_2") (pintype "passive"))
      (node (ref "MS33035") (pin "1") (pinfunction "1_1") (pintype "passive"))
    )
    (net (code "89") (name "Net-(1K,-Pad2)") (class "Default")
      (node (ref "1K,") (pin "2") (pinfunction "2_2") (pintype "passive"))
      (node (ref "MS33035") (pin "2") (pinfunction "2_2") (pintype "passive"))
    )
    (net (code "90") (name "Net-(1K_6-Pad2)") (class "Default")
      (node (ref "1K_6") (pin "2") (pinfunction "2_2") (pintype "passive"))
      (node (ref "500k_adj") (pin "1") (pinfunction "1_1") (pintype "passive"))
    )
    (net (code "91") (name "Net-(1uf_-Pad1)") (class "Default")
      (node (ref "1uf_") (pin "1") (pinfunction "1_1") (pintype "passive"))
      (node (ref "STM8S003F3P6") (pin "8") (pinfunction "8_8") (pintype "passive"))
    )
    (net (code "92") (name "Net-(2.2K,-Pad2)") (class "Default")
      (node (ref "2.2K,") (pin "2") (pinfunction "2_2") (pintype "passive"))
      (node (ref "47UF") (pin "2") (pinfunction "2_2") (pintype "passive"))
      (node (ref "RESET") (pin "1") (pinfunction "1_1") (pintype "passive"))
      (node (ref "锁存") (pin "1") (pinfunction "1_1") (pintype "passive"))
    )
    (net (code "93") (name "Net-(3_OR_4-Pad1)") (class "Default")
      (node (ref "3_OR_4") (pin "1") (pinfunction "1_1") (pintype "passive"))
      (node (ref "IS_COM_TOgnd") (pin "1") (pinfunction "1_1") (pintype "passive"))
    )
    (net (code "94") (name "Net-(10k_0-Pad1)") (class "Default")
      (node (ref "10k_0") (pin "1") (pinfunction "1_1") (pintype "passive"))
      (node (ref "CD4017") (pin "13") (pinfunction "13_13") (pintype "passive"))
    )
    (net (code "95") (name "Net-(10k_2_-Pad1)") (class "Default")
      (node (ref "10k_2_") (pin "1") (pinfunction "1_1") (pintype "passive"))
      (node (ref "4018_DIR") (pin "1") (pinfunction "1_1") (pintype "passive"))
      (node (ref "CD4070") (pin "1") (pinfunction "1_1") (pintype "passive"))
      (node (ref "CD4070") (pin "5") (pinfunction "5_5") (pintype "passive"))
    )
    (net (code "96") (name "Net-(10k_3_-Pad2)") (class "Default")
      (node (ref "10k_3_") (pin "2") (pinfunction "2_2") (pintype "passive"))
      (node (ref "4018_SHUT") (pin "2") (pinfunction "2_2") (pintype "passive"))
      (node (ref "CD4001") (pin "10") (pinfunction "10_10") (pintype "passive"))
      (node (ref "CD4001") (pin "2") (pinfunction "2_2") (pintype "passive"))
      (node (ref "CD4001") (pin "6") (pinfunction "6_6") (pintype "passive"))
    )
    (net (code "97") (name "Net-(18K-Pad1)") (class "Default")
      (node (ref "18K") (pin "1") (pinfunction "1_1") (pintype "passive"))
      (node (ref "5k_adj") (pin "1") (pinfunction "1_1") (pintype "passive"))
    )
    (net (code "98") (name "Net-(100p-Pad2)") (class "Default")
      (node (ref "100p") (pin "2") (pinfunction "2_2") (pintype "passive"))
      (node (ref "500k_adj") (pin "2") (pinfunction "2_2") (pintype "passive"))
      (node (ref "555") (pin "2") (pinfunction "2_2") (pintype "passive"))
      (node (ref "555") (pin "7") (pinfunction "7_7") (pintype "passive"))
    )
    (net (code "99") (name "Net-(104_555-Pad2)") (class "Default")
      (node (ref "104_555") (pin "2") (pinfunction "2_2") (pintype "passive"))
      (node (ref "555") (pin "8") (pinfunction "8_8") (pintype "passive"))
    )
    (net (code "100") (name "Net-(5817_0-A)") (class "Default")
      (node (ref "1K_5__") (pin "1") (pinfunction "1_1") (pintype "passive"))
      (node (ref "555") (pin "6") (pinfunction "6_6") (pintype "passive"))
      (node (ref "5817_0") (pin "1") (pinfunction "A_1") (pintype "passive"))
      (node (ref "5817_1") (pin "2") (pinfunction "K_2") (pintype "passive"))
    )
    (net (code "101") (name "Net-(5817_0-K)") (class "Default")
      (node (ref "500k_adj") (pin "3") (pinfunction "3_3") (pintype "passive"))
      (node (ref "5817_0") (pin "2") (pinfunction "K_2") (pintype "passive"))
    )
    (net (code "102") (name "Net-(5817_1,-A)") (class "Default")
      (node (ref "2.2K,") (pin "1") (pinfunction "1_1") (pintype "passive"))
      (node (ref "5817_1,") (pin "1") (pinfunction "A_1") (pintype "passive"))
    )
    (net (code "103") (name "Net-(5817_1-A)") (class "Default")
      (node (ref "1K_6") (pin "1") (pinfunction "1_1") (pintype "passive"))
      (node (ref "5817_1") (pin "1") (pinfunction "A_1") (pintype "passive"))
    )
    (net (code "104") (name "Net-(5824,,,-K)") (class "Default")
      (node (ref "470,,,") (pin "2") (pinfunction "2_2") (pintype "passive"))
      (node (ref "5824,,,") (pin "2") (pinfunction "K_2") (pintype "passive"))
      (node (ref "MS33035") (pin "18") (pinfunction "18_18") (pintype "passive"))
    )
    (net (code "105") (name "Net-(5824,,-K)") (class "Default")
      (node (ref "470,,") (pin "2") (pinfunction "2_2") (pintype "passive"))
      (node (ref "5824,,") (pin "2") (pinfunction "K_2") (pintype "passive"))
      (node (ref "MS33035") (pin "17") (pinfunction "17_17") (pintype "passive"))
    )
    (net (code "106") (name "Net-(5824,-K)") (class "Default")
      (node (ref "470,") (pin "2") (pinfunction "2_2") (pintype "passive"))
      (node (ref "5824,") (pin "2") (pinfunction "K_2") (pintype "passive"))
      (node (ref "MS33035") (pin "16") (pinfunction "16_16") (pintype "passive"))
    )
    (net (code "107") (name "Net-(5824-A)") (class "Default")
      (node (ref "0R_1") (pin "2") (pinfunction "2_2") (pintype "passive"))
      (node (ref "0R_2") (pin "2") (pinfunction "2_2") (pintype "passive"))
      (node (ref "5824") (pin "1") (pinfunction "A_1") (pintype "passive"))
      (node (ref "5824_1") (pin "1") (pinfunction "A_1") (pintype "passive"))
      (node (ref "5824_2") (pin "1") (pinfunction "A_1") (pintype "passive"))
    )
    (net (code "108") (name "Net-(5824_3-A)") (class "Default")
      (node (ref "5824_3") (pin "1") (pinfunction "A_1") (pintype "passive"))
      (node (ref "POWER_IN") (pin "1") (pinfunction "1_1") (pintype "passive"))
    )
    (net (code "109") (name "Net-(5824_3-K)") (class "Default")
      (node (ref "5824_3") (pin "2") (pinfunction "K_2") (pintype "passive"))
      (node (ref "POWER_SW") (pin "3") (pinfunction "3_3") (pintype "passive"))
    )
    (net (code "110") (name "Net-(CD4001-Pad3)") (class "Default")
      (node (ref "CD4001") (pin "3") (pinfunction "3_3") (pintype "passive"))
      (node (ref "UVW_OUT_4018") (pin "1") (pinfunction "1_1") (pintype "passive"))
    )
    (net (code "111") (name "Net-(CD4001-Pad4)") (class "Default")
      (node (ref "CD4001") (pin "4") (pinfunction "4_4") (pintype "passive"))
      (node (ref "UVW_OUT_4018") (pin "2") (pinfunction "2_2") (pintype "passive"))
    )
    (net (code "112") (name "Net-(CD4001-Pad11)") (class "Default")
      (node (ref "CD4001") (pin "11") (pinfunction "11_11") (pintype "passive"))
      (node (ref "UVW_OUT_4018") (pin "3") (pinfunction "3_3") (pintype "passive"))
    )
    (net (code "113") (name "Net-(DRV-A)") (class "Default")
      (node (ref "1K_3") (pin "1") (pinfunction "1_1") (pintype "passive"))
      (node (ref "DRV") (pin "1") (pinfunction "A_1") (pintype "passive"))
    )
    (net (code "114") (name "Net-(Fault-A)") (class "Default")
      (node (ref "2.2K") (pin "2") (pinfunction "2_2") (pintype "passive"))
      (node (ref "Fault") (pin "1") (pinfunction "A_1") (pintype "passive"))
    )
    (net (code "115") (name "Net-(LM358--IN1)") (class "Default")
      (node (ref "18K") (pin "2") (pinfunction "2_2") (pintype "passive"))
      (node (ref "1K_4_-") (pin "1") (pinfunction "1_1") (pintype "passive"))
      (node (ref "LM358") (pin "2") (pinfunction "-IN1_2") (pintype "passive"))
    )
    (net (code "116") (name "Net-(LM358-VEE)") (class "Default")
      (node (ref "0R_4") (pin "1") (pinfunction "1_1") (pintype "passive"))
      (node (ref "LM358") (pin "4") (pinfunction "VEE_4") (pintype "passive"))
    )
    (net (code "117") (name "Net-(MS33035-Pad11)") (class "Default")
      (node (ref "MS33035") (pin "11") (pinfunction "11_11") (pintype "passive"))
      (node (ref "SPEED") (pin "2") (pinfunction "2_2") (pintype "passive"))
    )
    (net (code "118") (name "Net-(PA3-A)") (class "Default")
      (node (ref "1K_5") (pin "1") (pinfunction "1_1") (pintype "passive"))
      (node (ref "PA3") (pin "1") (pinfunction "A_1") (pintype "passive"))
    )
    (net (code "119") (name "Net-(POWER-A)") (class "Default")
      (node (ref "1K_2") (pin "1") (pinfunction "1_1") (pintype "passive"))
      (node (ref "POWER") (pin "1") (pinfunction "A_1") (pintype "passive"))
    )
    (net (code "120") (name "Net-(STM8S003F3P6-SPI_MISO[TIM1_CH2])") (class "Default")
      (node (ref "I/O") (pin "4") (pinfunction "4_4") (pintype "passive"))
      (node (ref "STM8S003F3P6") (pin "17") (pinfunction "SPI_MISO[TIM1_CH2]_17") (pintype "passive"))
    )
    (net (code "121") (name "Net-(STM8S003F3P6-SPI_MOSI[TIM1_CH1])") (class "Default")
      (node (ref "I/O") (pin "5") (pinfunction "5_5") (pintype "passive"))
      (node (ref "STM8S003F3P6") (pin "16") (pinfunction "SPI_MOSI[TIM1_CH1]_16") (pintype "passive"))
    )
    (net (code "122") (name "Net-(STM8S003F3P6-SPI_SCK[TIM2_CH1])") (class "Default")
      (node (ref "I/O") (pin "6") (pinfunction "6_6") (pintype "passive"))
      (node (ref "STM8S003F3P6") (pin "15") (pinfunction "SPI_SCK[TIM2_CH1]_15") (pintype "passive"))
    )
    (net (code "123") (name "Net-(STM8S003F3P6-UART1_CK{slash}TIM2_CH1{slash}BEEP{slash}HS)") (class "Default")
      (node (ref "120R") (pin "1") (pinfunction "1_1") (pintype "passive"))
      (node (ref "STM8S003F3P6") (pin "1") (pinfunction "UART1_CK/TIM2_CH1/BEEP/HS_1") (pintype "passive"))
    )
    (net (code "124") (name "Net-(lock-A)") (class "Default")
      (node (ref "1K_1") (pin "1") (pinfunction "1_1") (pintype "passive"))
      (node (ref "lock") (pin "1") (pinfunction "A_1") (pintype "passive"))
    )
    (net (code "125") (name "Net-(stm8_power-A)") (class "Default")
      (node (ref "1K_4") (pin "1") (pinfunction "1_1") (pintype "passive"))
      (node (ref "stm8_power") (pin "1") (pinfunction "A_1") (pintype "passive"))
    )
    (net (code "126") (name "VCC") (class "Default")
      (node (ref "1000UF") (pin "1") (pinfunction "1_1") (pintype "passive"))
      (node (ref "104") (pin "1") (pinfunction "1_1") (pintype "passive"))
      (node (ref "104_2") (pin "2") (pinfunction "2_2") (pintype "passive"))
      (node (ref "1K_2") (pin "2") (pinfunction "2_2") (pintype "passive"))
      (node (ref "DRV_OPT") (pin "8") (pinfunction "B1_8") (pintype "passive"))
      (node (ref "LM2940") (pin "1") (pinfunction "Vi_1") (pintype "passive"))
      (node (ref "POWER_SW") (pin "2") (pinfunction "2_2") (pintype "passive"))
    )
    (net (code "127") (name "VCC_12V") (class "Default")
      (node (ref "104,-") (pin "2") (pinfunction "2_2") (pintype "passive"))
      (node (ref "220UF,") (pin "1") (pinfunction "1_1") (pintype "passive"))
      (node (ref "7812") (pin "3") (pinfunction "Vout_3") (pintype "passive"))
      (node (ref "MS33035") (pin "19") (pinfunction "19_19") (pintype "passive"))
    )
    (net (code "128") (name "VCC_DRV") (class "Default")
      (node (ref "10uf") (pin "2") (pinfunction "2_2") (pintype "passive"))
      (node (ref "1K_3") (pin "2") (pinfunction "2_2") (pintype "passive"))
      (node (ref "220UF") (pin "1") (pinfunction "1_1") (pintype "passive"))
      (node (ref "DRV11873") (pin "14") (pinfunction "14_14") (pintype "passive"))
      (node (ref "DRV_OPT") (pin "1") (pinfunction "A1_1") (pintype "passive"))
    )
    (net (code "129") (name "VCC_MC") (class "Default")
      (node (ref "1.1K") (pin "1") (pinfunction "1_1") (pintype "passive"))
      (node (ref "1.1K,") (pin "1") (pinfunction "1_1") (pintype "passive"))
      (node (ref "1.1K,,") (pin "1") (pinfunction "1_1") (pintype "passive"))
      (node (ref "1000UF,") (pin "1") (pinfunction "1_1") (pintype "passive"))
      (node (ref "104,") (pin "2") (pinfunction "2_2") (pintype "passive"))
      (node (ref "2.2K") (pin "1") (pinfunction "1_1") (pintype "passive"))
      (node (ref "220UF,,") (pin "1") (pinfunction "1_1") (pintype "passive"))
      (node (ref "7812") (pin "1") (pinfunction "Vin_1") (pintype "passive"))
      (node (ref "MS33035") (pin "20") (pinfunction "20_20") (pintype "passive"))
      (node (ref "POWER_MC") (pin "2") (pinfunction "2_2") (pintype "passive"))
    )
    (net (code "130") (name "unconnected-(CD4001-Pad12)") (class "Default")
      (node (ref "CD4001") (pin "12") (pinfunction "12_12") (pintype "passive"))
    )
    (net (code "131") (name "unconnected-(CD4001-Pad13)") (class "Default")
      (node (ref "CD4001") (pin "13") (pinfunction "13_13") (pintype "passive"))
    )
    (net (code "132") (name "unconnected-(CD4001-Pad14)") (class "Default")
      (node (ref "CD4001") (pin "14") (pinfunction "14_14") (pintype "passive"))
    )
    (net (code "133") (name "unconnected-(CD4013_-Pad9)") (class "Default")
      (node (ref "CD4013_") (pin "9") (pinfunction "9_9") (pintype "passive"))
    )
    (net (code "134") (name "unconnected-(CD4013_-Pad10)") (class "Default")
      (node (ref "CD4013_") (pin "10") (pinfunction "10_10") (pintype "passive"))
    )
    (net (code "135") (name "unconnected-(CD4013_-Pad11)") (class "Default")
      (node (ref "CD4013_") (pin "11") (pinfunction "11_11") (pintype "passive"))
    )
    (net (code "136") (name "unconnected-(CD4013_-Pad12)") (class "Default")
      (node (ref "CD4013_") (pin "12") (pinfunction "12_12") (pintype "passive"))
    )
    (net (code "137") (name "unconnected-(CD4013_-Pad13)") (class "Default")
      (node (ref "CD4013_") (pin "13") (pinfunction "13_13") (pintype "passive"))
    )
    (net (code "138") (name "unconnected-(CD4013_-Pad14)") (class "Default")
      (node (ref "CD4013_") (pin "14") (pinfunction "14_14") (pintype "passive"))
    )
    (net (code "139") (name "unconnected-(CD4018-Pad3)") (class "Default")
      (node (ref "CD4018") (pin "3") (pinfunction "3_3") (pintype "passive+no_connect"))
    )
    (net (code "140") (name "unconnected-(CD4018-Pad4)") (class "Default")
      (node (ref "CD4018") (pin "4") (pinfunction "4_4") (pintype "passive+no_connect"))
    )
    (net (code "141") (name "unconnected-(CD4018-Pad13)") (class "Default")
      (node (ref "CD4018") (pin "13") (pinfunction "13_13") (pintype "passive+no_connect"))
    )
    (net (code "142") (name "unconnected-(CD4018-Pad14)") (class "Default")
      (node (ref "CD4018") (pin "14") (pinfunction "14_14") (pintype "passive+no_connect"))
    )
    (net (code "143") (name "unconnected-(CD4018-Pad16)") (class "Default")
      (node (ref "CD4018") (pin "16") (pinfunction "16_16") (pintype "passive+no_connect"))
    )
    (net (code "144") (name "unconnected-(CD4070-Pad9)") (class "Default")
      (node (ref "CD4070") (pin "9") (pinfunction "9_9") (pintype "passive"))
    )
    (net (code "145") (name "unconnected-(CD4070-Pad10)") (class "Default")
      (node (ref "CD4070") (pin "10") (pinfunction "10_10") (pintype "passive"))
    )
    (net (code "146") (name "unconnected-(CD4070-Pad11)") (class "Default")
      (node (ref "CD4070") (pin "11") (pinfunction "11_11") (pintype "passive"))
    )
    (net (code "147") (name "unconnected-(CD4070-Pad12)") (class "Default")
      (node (ref "CD4070") (pin "12") (pinfunction "12_12") (pintype "passive"))
    )
    (net (code "148") (name "unconnected-(CD4070-Pad13)") (class "Default")
      (node (ref "CD4070") (pin "13") (pinfunction "13_13") (pintype "passive"))
    )
    (net (code "149") (name "unconnected-(CD4070-Pad14)") (class "Default")
      (node (ref "CD4070") (pin "14") (pinfunction "14_14") (pintype "passive"))
    )
    (net (code "150") (name "unconnected-(DIG_POWER-Pad1)") (class "Default")
      (node (ref "DIG_POWER") (pin "1") (pinfunction "1_1") (pintype "passive"))
    )
    (net (code "151") (name "unconnected-(LM358-+IN2-Pad5)") (class "Default")
      (node (ref "LM358") (pin "5") (pinfunction "+IN2_5") (pintype "passive"))
    )
    (net (code "152") (name "unconnected-(LM358--IN2-Pad6)") (class "Default")
      (node (ref "LM358") (pin "6") (pinfunction "-IN2_6") (pintype "passive"))
    )
    (net (code "153") (name "unconnected-(LM358-OUT2-Pad7)") (class "Default")
      (node (ref "LM358") (pin "7") (pinfunction "OUT2_7") (pintype "passive"))
    )
    (net (code "154") (name "unconnected-(POWER_SW-Pad1)") (class "Default")
      (node (ref "POWER_SW") (pin "1") (pinfunction "1_1") (pintype "passive"))
    )
  )
)
